# Noctua_2.net
KiCad netlist of a schematic drawn in EAGLE
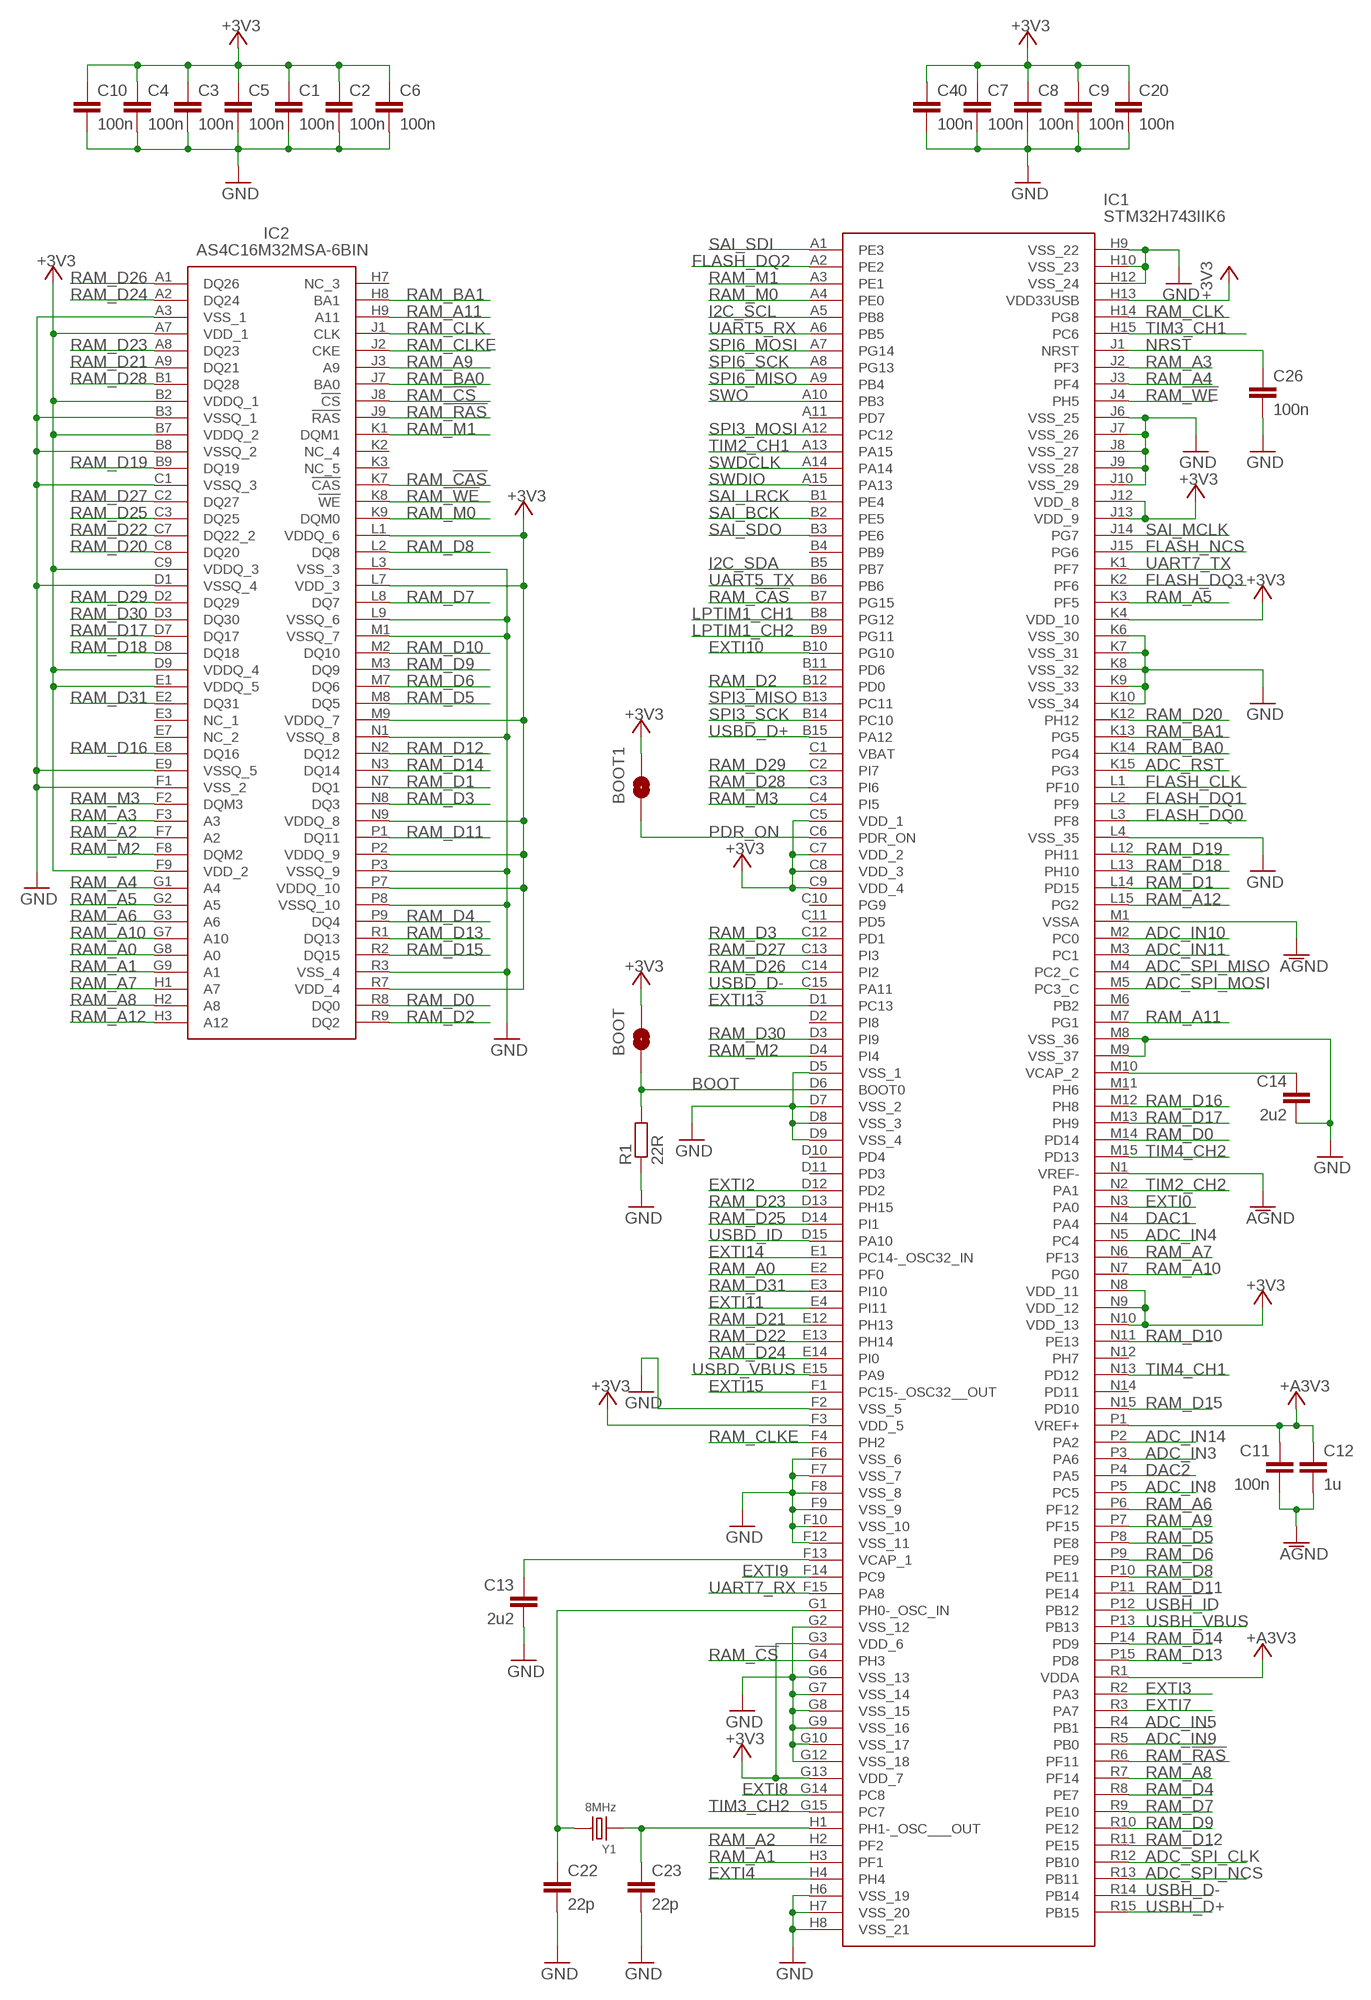
[diagram p0: schematic, sheet 1, part 1 of 2]
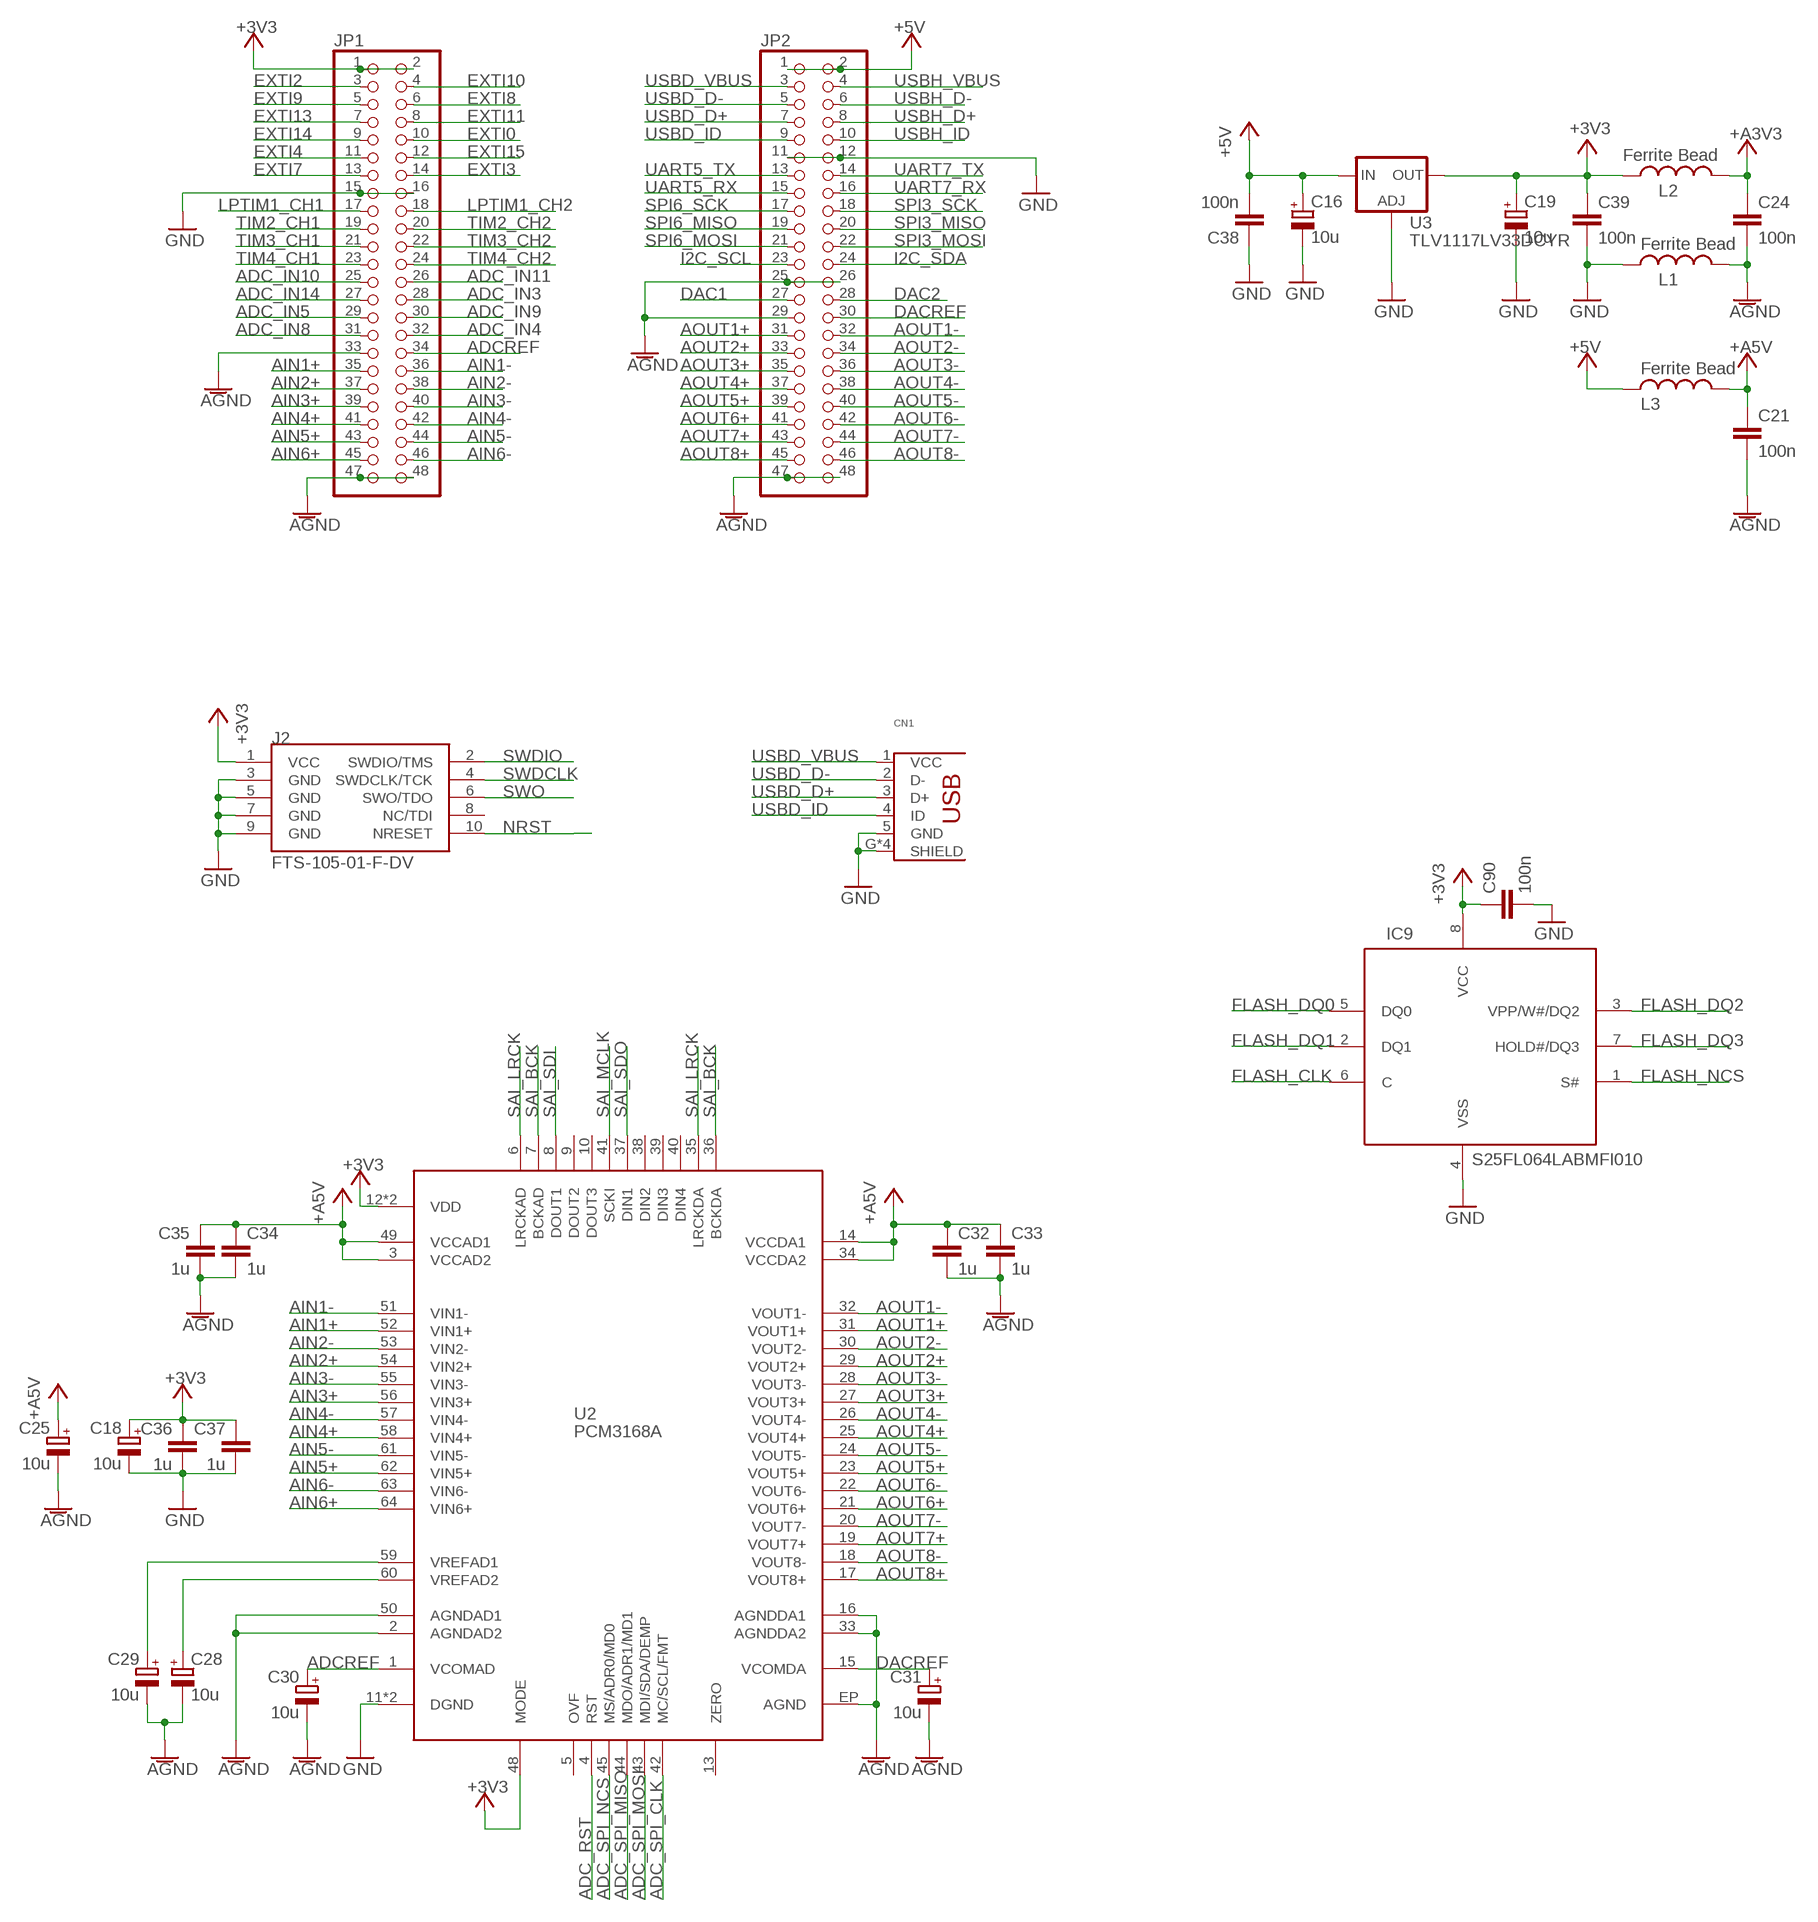
[diagram p1: schematic, sheet 1, part 2 of 2]

(export (version "E")
  (design (tool "Eeschema 10.0.6"))
  (components
    (comp (ref "BOOT")
      (value "SOLDERJUMPERNO")
      (footprint "eagle-import:SJ_2S-NO")
      (libsource (lib "eagle-import") (part "SOLDERJUMPERNO"))
    )
    (comp (ref "BOOT1")
      (value "SOLDERJUMPERNO")
      (footprint "eagle-import:SJ_2S-NO")
      (libsource (lib "eagle-import") (part "SOLDERJUMPERNO"))
    )
    (comp (ref "C1")
      (value "100n")
      (footprint "eagle-import:C0402")
      (libsource (lib "eagle-import") (part "C-EUC0402"))
    )
    (comp (ref "C2")
      (value "100n")
      (footprint "eagle-import:C0402")
      (libsource (lib "eagle-import") (part "C-EUC0402"))
    )
    (comp (ref "C3")
      (value "100n")
      (footprint "eagle-import:C0402")
      (libsource (lib "eagle-import") (part "C-EUC0402"))
    )
    (comp (ref "C4")
      (value "100n")
      (footprint "eagle-import:C0402")
      (libsource (lib "eagle-import") (part "C-EUC0402"))
    )
    (comp (ref "C5")
      (value "100n")
      (footprint "eagle-import:C0402")
      (libsource (lib "eagle-import") (part "C-EUC0402"))
    )
    (comp (ref "C6")
      (value "100n")
      (footprint "eagle-import:C0402")
      (libsource (lib "eagle-import") (part "C-EUC0402"))
    )
    (comp (ref "C7")
      (value "100n")
      (footprint "eagle-import:C0402")
      (libsource (lib "eagle-import") (part "C-EUC0402"))
    )
    (comp (ref "C8")
      (value "100n")
      (footprint "eagle-import:C0402")
      (libsource (lib "eagle-import") (part "C-EUC0402"))
    )
    (comp (ref "C9")
      (value "100n")
      (footprint "eagle-import:C0402")
      (libsource (lib "eagle-import") (part "C-EUC0402"))
    )
    (comp (ref "C10")
      (value "100n")
      (footprint "eagle-import:C0402")
      (libsource (lib "eagle-import") (part "C-EUC0402"))
    )
    (comp (ref "C11")
      (value "100n")
      (footprint "eagle-import:C0402")
      (libsource (lib "eagle-import") (part "C-EUC0402"))
    )
    (comp (ref "C12")
      (value "1u")
      (footprint "eagle-import:C0402")
      (libsource (lib "eagle-import") (part "C-EUC0402"))
    )
    (comp (ref "C13")
      (value "2u2")
      (footprint "eagle-import:C0402")
      (libsource (lib "eagle-import") (part "C-EUC0402"))
    )
    (comp (ref "C14")
      (value "2u2")
      (footprint "eagle-import:C0402")
      (libsource (lib "eagle-import") (part "C-EUC0402"))
    )
    (comp (ref "C16")
      (value "10u")
      (footprint "eagle-import:UD-4X5,8_NICHICON")
      (libsource (lib "eagle-import") (part "CPOL-EUUD-4X5,8"))
    )
    (comp (ref "C18")
      (value "10u")
      (footprint "eagle-import:UD-4X5,8_NICHICON")
      (libsource (lib "eagle-import") (part "CPOL-EUUD-4X5,8"))
    )
    (comp (ref "C19")
      (value "10u")
      (footprint "eagle-import:UD-4X5,8_NICHICON")
      (libsource (lib "eagle-import") (part "CPOL-EUUD-4X5,8"))
    )
    (comp (ref "C20")
      (value "100n")
      (footprint "eagle-import:C0402")
      (libsource (lib "eagle-import") (part "C-EUC0402"))
    )
    (comp (ref "C21")
      (value "100n")
      (footprint "eagle-import:C0603")
      (libsource (lib "eagle-import") (part "C-EUC0603"))
    )
    (comp (ref "C22")
      (value "22p")
      (footprint "eagle-import:C0402")
      (libsource (lib "eagle-import") (part "C-EUC0402"))
    )
    (comp (ref "C23")
      (value "22p")
      (footprint "eagle-import:C0402")
      (libsource (lib "eagle-import") (part "C-EUC0402"))
    )
    (comp (ref "C24")
      (value "100n")
      (footprint "eagle-import:C0402")
      (libsource (lib "eagle-import") (part "C-EUC0402"))
    )
    (comp (ref "C25")
      (value "10u")
      (footprint "eagle-import:UD-4X5,8_NICHICON")
      (libsource (lib "eagle-import") (part "CPOL-EUUD-4X5,8"))
    )
    (comp (ref "C26")
      (value "100n")
      (footprint "eagle-import:C0402")
      (libsource (lib "eagle-import") (part "C-EUC0402"))
    )
    (comp (ref "C28")
      (value "10u")
      (footprint "eagle-import:UD-4X5,8_NICHICON")
      (libsource (lib "eagle-import") (part "CPOL-EUUD-4X5,8"))
    )
    (comp (ref "C29")
      (value "10u")
      (footprint "eagle-import:UD-4X5,8_NICHICON")
      (libsource (lib "eagle-import") (part "CPOL-EUUD-4X5,8"))
    )
    (comp (ref "C30")
      (value "10u")
      (footprint "eagle-import:UD-4X5,8_NICHICON")
      (libsource (lib "eagle-import") (part "CPOL-EUUD-4X5,8"))
    )
    (comp (ref "C31")
      (value "10u")
      (footprint "eagle-import:UD-4X5,8_NICHICON")
      (libsource (lib "eagle-import") (part "CPOL-EUUD-4X5,8"))
    )
    (comp (ref "C32")
      (value "1u")
      (footprint "eagle-import:C0603")
      (libsource (lib "eagle-import") (part "C-EUC0603"))
    )
    (comp (ref "C33")
      (value "1u")
      (footprint "eagle-import:C0603")
      (libsource (lib "eagle-import") (part "C-EUC0603"))
    )
    (comp (ref "C34")
      (value "1u")
      (footprint "eagle-import:C0603")
      (libsource (lib "eagle-import") (part "C-EUC0603"))
    )
    (comp (ref "C35")
      (value "1u")
      (footprint "eagle-import:C0603")
      (libsource (lib "eagle-import") (part "C-EUC0603"))
    )
    (comp (ref "C36")
      (value "1u")
      (footprint "eagle-import:C0603")
      (libsource (lib "eagle-import") (part "C-EUC0603"))
    )
    (comp (ref "C37")
      (value "1u")
      (footprint "eagle-import:C0603")
      (libsource (lib "eagle-import") (part "C-EUC0603"))
    )
    (comp (ref "C38")
      (value "100n")
      (footprint "eagle-import:C0402")
      (libsource (lib "eagle-import") (part "C-EUC0402"))
    )
    (comp (ref "C39")
      (value "100n")
      (footprint "eagle-import:C0402")
      (libsource (lib "eagle-import") (part "C-EUC0402"))
    )
    (comp (ref "C40")
      (value "100n")
      (footprint "eagle-import:C0402")
      (libsource (lib "eagle-import") (part "C-EUC0402"))
    )
    (comp (ref "C90")
      (value "100n")
      (footprint "eagle-import:C0402")
      (libsource (lib "eagle-import") (part "C-EUC0402"))
    )
    (comp (ref "CN1")
      (value "USB_HRS_ZX62-B-5PA(11)MICRO.B")
      (footprint "eagle-import:HRS_ZX62RD-AB-5P8")
      (libsource (lib "eagle-import") (part "USB_HRS_ZX62-B-5PA(11)MICRO.B"))
    )
    (comp (ref "IC1")
      (value "STM32H743IIK6")
      (footprint "eagle-import:BGA201C65P15X15_1000X1000X60")
      (fields (field (name "MOUSER_PART_NUMBER") "511-STM32H743IIK6"))
      (libsource (lib "eagle-import") (part "STM32H743IIK6"))
    )
    (comp (ref "IC2")
      (value "AS4C16M32MSA-6BIN")
      (footprint "eagle-import:BGA90C80P9X15_800X1300X100")
      (fields (field (name "MOUSER_PART_NUMBER") "913-AS4C16M32MSA6BIN"))
      (libsource (lib "eagle-import") (part "AS4C16M32MSA-6BIN"))
    )
    (comp (ref "IC9")
      (value "S25FL064LABMFI010")
      (footprint "eagle-import:SO8W")
      (libsource (lib "eagle-import") (part "N25Q128A13"))
    )
    (comp (ref "J2")
      (value "FTS-105-01-F-DV")
      (footprint "eagle-import:2X5_1.27MM_SMD")
      (libsource (lib "eagle-import") (part "ARM_10SMD"))
    )
    (comp (ref "JP1")
      (value "PINHD-2X24")
      (footprint "eagle-import:2X24")
      (libsource (lib "eagle-import") (part "PINHD-2X24"))
    )
    (comp (ref "JP2")
      (value "PINHD-2X24")
      (footprint "eagle-import:2X24")
      (libsource (lib "eagle-import") (part "PINHD-2X24"))
    )
    (comp (ref "L1")
      (value "Ferrite Bead")
      (footprint "eagle-import:0603")
      (libsource (lib "eagle-import") (part "INDUCTOR"))
    )
    (comp (ref "L2")
      (value "Ferrite Bead")
      (footprint "eagle-import:0603")
      (libsource (lib "eagle-import") (part "INDUCTOR"))
    )
    (comp (ref "L3")
      (value "Ferrite Bead")
      (footprint "eagle-import:0603")
      (libsource (lib "eagle-import") (part "INDUCTOR"))
    )
    (comp (ref "R1")
      (value "22R")
      (footprint "eagle-import:0603")
      (libsource (lib "eagle-import") (part "R-EU_0603"))
    )
    (comp (ref "U2")
      (value "PCM3168A")
      (footprint "eagle-import:PQFP64")
      (libsource (lib "eagle-import") (part "PCM3168A"))
    )
    (comp (ref "U3")
      (value "TLV1117LV33DCYR")
      (footprint "eagle-import:SOT223")
      (libsource (lib "eagle-import") (part "LD117A?S33TR"))
    )
    (comp (ref "Y1")
      (value "8MHz")
      (footprint "eagle-import:X2-SMD-5.0X3.2X1.3MM")
      (fields (field (name "MPN") "5032/2P"))
      (libsource (lib "eagle-import") (part "SMD-CRYSTAL-8MHZ-20PF-20PPM(2P-5.0X3.2MM)"))
    )
  )
  (nets
    (net (code "1") (name "+3V3") (class "Default")
      (node (ref "BOOT") (pin "1") (pinfunction "1_1") (pintype "passive"))
      (node (ref "BOOT1") (pin "1") (pinfunction "1_1") (pintype "passive"))
      (node (ref "C1") (pin "1") (pinfunction "1_1") (pintype "passive"))
      (node (ref "C10") (pin "1") (pinfunction "1_1") (pintype "passive"))
      (node (ref "C18") (pin "+") (pinfunction "+_+") (pintype "passive"))
      (node (ref "C19") (pin "+") (pinfunction "+_+") (pintype "passive"))
      (node (ref "C2") (pin "1") (pinfunction "1_1") (pintype "passive"))
      (node (ref "C20") (pin "1") (pinfunction "1_1") (pintype "passive"))
      (node (ref "C3") (pin "1") (pinfunction "1_1") (pintype "passive"))
      (node (ref "C36") (pin "1") (pinfunction "1_1") (pintype "passive"))
      (node (ref "C37") (pin "1") (pinfunction "1_1") (pintype "passive"))
      (node (ref "C39") (pin "1") (pinfunction "1_1") (pintype "passive"))
      (node (ref "C4") (pin "1") (pinfunction "1_1") (pintype "passive"))
      (node (ref "C40") (pin "1") (pinfunction "1_1") (pintype "passive"))
      (node (ref "C5") (pin "1") (pinfunction "1_1") (pintype "passive"))
      (node (ref "C6") (pin "1") (pinfunction "1_1") (pintype "passive"))
      (node (ref "C7") (pin "1") (pinfunction "1_1") (pintype "passive"))
      (node (ref "C8") (pin "1") (pinfunction "1_1") (pintype "passive"))
      (node (ref "C9") (pin "1") (pinfunction "1_1") (pintype "passive"))
      (node (ref "C90") (pin "1") (pinfunction "1_1") (pintype "passive"))
      (node (ref "IC1") (pin "C5") (pinfunction "VDD_1_C5") (pintype "bidirectional"))
      (node (ref "IC1") (pin "C7") (pinfunction "VDD_2_C7") (pintype "bidirectional"))
      (node (ref "IC1") (pin "C8") (pinfunction "VDD_3_C8") (pintype "bidirectional"))
      (node (ref "IC1") (pin "C9") (pinfunction "VDD_4_C9") (pintype "bidirectional"))
      (node (ref "IC1") (pin "F3") (pinfunction "VDD_5_F3") (pintype "bidirectional"))
      (node (ref "IC1") (pin "G13") (pinfunction "VDD_7_G13") (pintype "bidirectional"))
      (node (ref "IC1") (pin "G3") (pinfunction "VDD_6_G3") (pintype "bidirectional"))
      (node (ref "IC1") (pin "H13") (pinfunction "VDD33USB_H13") (pintype "bidirectional"))
      (node (ref "IC1") (pin "J12") (pinfunction "VDD_8_J12") (pintype "bidirectional"))
      (node (ref "IC1") (pin "J13") (pinfunction "VDD_9_J13") (pintype "bidirectional"))
      (node (ref "IC1") (pin "K4") (pinfunction "VDD_10_K4") (pintype "bidirectional"))
      (node (ref "IC1") (pin "N10") (pinfunction "VDD_13_N10") (pintype "bidirectional"))
      (node (ref "IC1") (pin "N8") (pinfunction "VDD_11_N8") (pintype "bidirectional"))
      (node (ref "IC1") (pin "N9") (pinfunction "VDD_12_N9") (pintype "bidirectional"))
      (node (ref "IC2") (pin "A7") (pinfunction "VDD_1_A7") (pintype "bidirectional"))
      (node (ref "IC2") (pin "B2") (pinfunction "VDDQ_1_B2") (pintype "bidirectional"))
      (node (ref "IC2") (pin "B7") (pinfunction "VDDQ_2_B7") (pintype "bidirectional"))
      (node (ref "IC2") (pin "C9") (pinfunction "VDDQ_3_C9") (pintype "bidirectional"))
      (node (ref "IC2") (pin "D9") (pinfunction "VDDQ_4_D9") (pintype "bidirectional"))
      (node (ref "IC2") (pin "E1") (pinfunction "VDDQ_5_E1") (pintype "bidirectional"))
      (node (ref "IC2") (pin "F9") (pinfunction "VDD_2_F9") (pintype "bidirectional"))
      (node (ref "IC2") (pin "L1") (pinfunction "VDDQ_6_L1") (pintype "bidirectional"))
      (node (ref "IC2") (pin "L7") (pinfunction "VDD_3_L7") (pintype "bidirectional"))
      (node (ref "IC2") (pin "M9") (pinfunction "VDDQ_7_M9") (pintype "bidirectional"))
      (node (ref "IC2") (pin "N9") (pinfunction "VDDQ_8_N9") (pintype "bidirectional"))
      (node (ref "IC2") (pin "P2") (pinfunction "VDDQ_9_P2") (pintype "bidirectional"))
      (node (ref "IC2") (pin "P7") (pinfunction "VDDQ_10_P7") (pintype "bidirectional"))
      (node (ref "IC2") (pin "R7") (pinfunction "VDD_4_R7") (pintype "bidirectional"))
      (node (ref "IC9") (pin "8") (pinfunction "VCC_8") (pintype "bidirectional"))
      (node (ref "J2") (pin "1") (pinfunction "VCC_1") (pintype "bidirectional"))
      (node (ref "JP1") (pin "1") (pinfunction "1_1") (pintype "passive"))
      (node (ref "JP1") (pin "2") (pinfunction "2_2") (pintype "passive"))
      (node (ref "L2") (pin "2") (pinfunction "2_2") (pintype "passive"))
      (node (ref "U2") (pin "12") (pinfunction "VDD_12") (pintype "bidirectional"))
      (node (ref "U2") (pin "46") (pinfunction "VDD_46") (pintype "bidirectional"))
      (node (ref "U2") (pin "48") (pinfunction "MODE_48") (pintype "bidirectional"))
      (node (ref "U3") (pin "4") (pinfunction "OUT_4") (pintype "passive"))
    )
    (net (code "2") (name "+5V") (class "Default")
      (node (ref "C16") (pin "+") (pinfunction "+_+") (pintype "passive"))
      (node (ref "C38") (pin "2") (pinfunction "2_2") (pintype "passive"))
      (node (ref "JP2") (pin "1") (pinfunction "1_1") (pintype "passive"))
      (node (ref "JP2") (pin "2") (pinfunction "2_2") (pintype "passive"))
      (node (ref "L3") (pin "2") (pinfunction "2_2") (pintype "passive"))
      (node (ref "U3") (pin "3") (pinfunction "IN_3") (pintype "input"))
    )
    (net (code "3") (name "+A3V3") (class "Default")
      (node (ref "C11") (pin "1") (pinfunction "1_1") (pintype "passive"))
      (node (ref "C12") (pin "1") (pinfunction "1_1") (pintype "passive"))
      (node (ref "C24") (pin "1") (pinfunction "1_1") (pintype "passive"))
      (node (ref "IC1") (pin "P1") (pinfunction "VREF+_P1") (pintype "bidirectional"))
      (node (ref "IC1") (pin "R1") (pinfunction "VDDA_R1") (pintype "bidirectional"))
      (node (ref "L2") (pin "1") (pinfunction "1_1") (pintype "passive"))
    )
    (net (code "4") (name "+A5V") (class "Default")
      (node (ref "C21") (pin "1") (pinfunction "1_1") (pintype "passive"))
      (node (ref "C25") (pin "+") (pinfunction "+_+") (pintype "passive"))
      (node (ref "C32") (pin "1") (pinfunction "1_1") (pintype "passive"))
      (node (ref "C33") (pin "1") (pinfunction "1_1") (pintype "passive"))
      (node (ref "C34") (pin "1") (pinfunction "1_1") (pintype "passive"))
      (node (ref "C35") (pin "1") (pinfunction "1_1") (pintype "passive"))
      (node (ref "L3") (pin "1") (pinfunction "1_1") (pintype "passive"))
      (node (ref "U2") (pin "14") (pinfunction "VCCDA1_14") (pintype "bidirectional"))
      (node (ref "U2") (pin "3") (pinfunction "VCCAD2_3") (pintype "bidirectional"))
      (node (ref "U2") (pin "34") (pinfunction "VCCDA2_34") (pintype "bidirectional"))
      (node (ref "U2") (pin "49") (pinfunction "VCCAD1_49") (pintype "bidirectional"))
    )
    (net (code "5") (name "/ADCREF") (class "Default")
      (node (ref "C30") (pin "+") (pinfunction "+_+") (pintype "passive"))
      (node (ref "JP1") (pin "34") (pinfunction "34_34") (pintype "passive"))
      (node (ref "U2") (pin "1") (pinfunction "VCOMAD_1") (pintype "bidirectional"))
    )
    (net (code "6") (name "/ADC_IN3") (class "Default")
      (node (ref "IC1") (pin "P3") (pinfunction "PA6_P3") (pintype "bidirectional"))
      (node (ref "JP1") (pin "28") (pinfunction "28_28") (pintype "passive"))
    )
    (net (code "7") (name "/ADC_IN4") (class "Default")
      (node (ref "IC1") (pin "N5") (pinfunction "PC4_N5") (pintype "bidirectional"))
      (node (ref "JP1") (pin "32") (pinfunction "32_32") (pintype "passive"))
    )
    (net (code "8") (name "/ADC_IN5") (class "Default")
      (node (ref "IC1") (pin "R4") (pinfunction "PB1_R4") (pintype "bidirectional"))
      (node (ref "JP1") (pin "29") (pinfunction "29_29") (pintype "passive"))
    )
    (net (code "9") (name "/ADC_IN8") (class "Default")
      (node (ref "IC1") (pin "P5") (pinfunction "PC5_P5") (pintype "bidirectional"))
      (node (ref "JP1") (pin "31") (pinfunction "31_31") (pintype "passive"))
    )
    (net (code "10") (name "/ADC_IN9") (class "Default")
      (node (ref "IC1") (pin "R5") (pinfunction "PB0_R5") (pintype "bidirectional"))
      (node (ref "JP1") (pin "30") (pinfunction "30_30") (pintype "passive"))
    )
    (net (code "11") (name "/ADC_IN10") (class "Default")
      (node (ref "IC1") (pin "M2") (pinfunction "PC0_M2") (pintype "bidirectional"))
      (node (ref "JP1") (pin "25") (pinfunction "25_25") (pintype "passive"))
    )
    (net (code "12") (name "/ADC_IN11") (class "Default")
      (node (ref "IC1") (pin "M3") (pinfunction "PC1_M3") (pintype "bidirectional"))
      (node (ref "JP1") (pin "26") (pinfunction "26_26") (pintype "passive"))
    )
    (net (code "13") (name "/ADC_IN14") (class "Default")
      (node (ref "IC1") (pin "P2") (pinfunction "PA2_P2") (pintype "bidirectional"))
      (node (ref "JP1") (pin "27") (pinfunction "27_27") (pintype "passive"))
    )
    (net (code "14") (name "/ADC_RST") (class "Default")
      (node (ref "IC1") (pin "K15") (pinfunction "PG3_K15") (pintype "bidirectional"))
      (node (ref "U2") (pin "4") (pinfunction "RST_4") (pintype "bidirectional"))
    )
    (net (code "15") (name "/ADC_SPI_CLK") (class "Default")
      (node (ref "IC1") (pin "R12") (pinfunction "PB10_R12") (pintype "bidirectional"))
      (node (ref "U2") (pin "42") (pinfunction "MC/SCL/FMT_42") (pintype "bidirectional"))
    )
    (net (code "16") (name "/ADC_SPI_MISO") (class "Default")
      (node (ref "IC1") (pin "M4") (pinfunction "PC2_C_M4") (pintype "bidirectional"))
      (node (ref "U2") (pin "44") (pinfunction "MDO/ADR1/MD1_44") (pintype "bidirectional"))
    )
    (net (code "17") (name "/ADC_SPI_MOSI") (class "Default")
      (node (ref "IC1") (pin "M5") (pinfunction "PC3_C_M5") (pintype "bidirectional"))
      (node (ref "U2") (pin "43") (pinfunction "MDI/SDA/DEMP_43") (pintype "bidirectional"))
    )
    (net (code "18") (name "/ADC_SPI_NCS") (class "Default")
      (node (ref "IC1") (pin "R13") (pinfunction "PB11_R13") (pintype "bidirectional"))
      (node (ref "U2") (pin "45") (pinfunction "MS/ADR0/MD0_45") (pintype "bidirectional"))
    )
    (net (code "19") (name "/AIN1+") (class "Default")
      (node (ref "JP1") (pin "35") (pinfunction "35_35") (pintype "passive"))
      (node (ref "U2") (pin "52") (pinfunction "VIN1+_52") (pintype "bidirectional"))
    )
    (net (code "20") (name "/AIN1-") (class "Default")
      (node (ref "JP1") (pin "36") (pinfunction "36_36") (pintype "passive"))
      (node (ref "U2") (pin "51") (pinfunction "VIN1-_51") (pintype "bidirectional"))
    )
    (net (code "21") (name "/AIN2+") (class "Default")
      (node (ref "JP1") (pin "37") (pinfunction "37_37") (pintype "passive"))
      (node (ref "U2") (pin "54") (pinfunction "VIN2+_54") (pintype "bidirectional"))
    )
    (net (code "22") (name "/AIN2-") (class "Default")
      (node (ref "JP1") (pin "38") (pinfunction "38_38") (pintype "passive"))
      (node (ref "U2") (pin "53") (pinfunction "VIN2-_53") (pintype "bidirectional"))
    )
    (net (code "23") (name "/AIN3+") (class "Default")
      (node (ref "JP1") (pin "39") (pinfunction "39_39") (pintype "passive"))
      (node (ref "U2") (pin "56") (pinfunction "VIN3+_56") (pintype "bidirectional"))
    )
    (net (code "24") (name "/AIN3-") (class "Default")
      (node (ref "JP1") (pin "40") (pinfunction "40_40") (pintype "passive"))
      (node (ref "U2") (pin "55") (pinfunction "VIN3-_55") (pintype "bidirectional"))
    )
    (net (code "25") (name "/AIN4+") (class "Default")
      (node (ref "JP1") (pin "41") (pinfunction "41_41") (pintype "passive"))
      (node (ref "U2") (pin "58") (pinfunction "VIN4+_58") (pintype "bidirectional"))
    )
    (net (code "26") (name "/AIN4-") (class "Default")
      (node (ref "JP1") (pin "42") (pinfunction "42_42") (pintype "passive"))
      (node (ref "U2") (pin "57") (pinfunction "VIN4-_57") (pintype "bidirectional"))
    )
    (net (code "27") (name "/AIN5+") (class "Default")
      (node (ref "JP1") (pin "43") (pinfunction "43_43") (pintype "passive"))
      (node (ref "U2") (pin "62") (pinfunction "VIN5+_62") (pintype "bidirectional"))
    )
    (net (code "28") (name "/AIN5-") (class "Default")
      (node (ref "JP1") (pin "44") (pinfunction "44_44") (pintype "passive"))
      (node (ref "U2") (pin "61") (pinfunction "VIN5-_61") (pintype "bidirectional"))
    )
    (net (code "29") (name "/AIN6+") (class "Default")
      (node (ref "JP1") (pin "45") (pinfunction "45_45") (pintype "passive"))
      (node (ref "U2") (pin "64") (pinfunction "VIN6+_64") (pintype "bidirectional"))
    )
    (net (code "30") (name "/AIN6-") (class "Default")
      (node (ref "JP1") (pin "46") (pinfunction "46_46") (pintype "passive"))
      (node (ref "U2") (pin "63") (pinfunction "VIN6-_63") (pintype "bidirectional"))
    )
    (net (code "31") (name "/AOUT1+") (class "Default")
      (node (ref "JP2") (pin "31") (pinfunction "31_31") (pintype "passive"))
      (node (ref "U2") (pin "31") (pinfunction "VOUT1+_31") (pintype "bidirectional"))
    )
    (net (code "32") (name "/AOUT1-") (class "Default")
      (node (ref "JP2") (pin "32") (pinfunction "32_32") (pintype "passive"))
      (node (ref "U2") (pin "32") (pinfunction "VOUT1-_32") (pintype "bidirectional"))
    )
    (net (code "33") (name "/AOUT2+") (class "Default")
      (node (ref "JP2") (pin "33") (pinfunction "33_33") (pintype "passive"))
      (node (ref "U2") (pin "29") (pinfunction "VOUT2+_29") (pintype "bidirectional"))
    )
    (net (code "34") (name "/AOUT2-") (class "Default")
      (node (ref "JP2") (pin "34") (pinfunction "34_34") (pintype "passive"))
      (node (ref "U2") (pin "30") (pinfunction "VOUT2-_30") (pintype "bidirectional"))
    )
    (net (code "35") (name "/AOUT3+") (class "Default")
      (node (ref "JP2") (pin "35") (pinfunction "35_35") (pintype "passive"))
      (node (ref "U2") (pin "27") (pinfunction "VOUT3+_27") (pintype "bidirectional"))
    )
    (net (code "36") (name "/AOUT3-") (class "Default")
      (node (ref "JP2") (pin "36") (pinfunction "36_36") (pintype "passive"))
      (node (ref "U2") (pin "28") (pinfunction "VOUT3-_28") (pintype "bidirectional"))
    )
    (net (code "37") (name "/AOUT4+") (class "Default")
      (node (ref "JP2") (pin "37") (pinfunction "37_37") (pintype "passive"))
      (node (ref "U2") (pin "25") (pinfunction "VOUT4+_25") (pintype "bidirectional"))
    )
    (net (code "38") (name "/AOUT4-") (class "Default")
      (node (ref "JP2") (pin "38") (pinfunction "38_38") (pintype "passive"))
      (node (ref "U2") (pin "26") (pinfunction "VOUT4-_26") (pintype "bidirectional"))
    )
    (net (code "39") (name "/AOUT5+") (class "Default")
      (node (ref "JP2") (pin "39") (pinfunction "39_39") (pintype "passive"))
      (node (ref "U2") (pin "23") (pinfunction "VOUT5+_23") (pintype "bidirectional"))
    )
    (net (code "40") (name "/AOUT5-") (class "Default")
      (node (ref "JP2") (pin "40") (pinfunction "40_40") (pintype "passive"))
      (node (ref "U2") (pin "24") (pinfunction "VOUT5-_24") (pintype "bidirectional"))
    )
    (net (code "41") (name "/AOUT6+") (class "Default")
      (node (ref "JP2") (pin "41") (pinfunction "41_41") (pintype "passive"))
      (node (ref "U2") (pin "21") (pinfunction "VOUT6+_21") (pintype "bidirectional"))
    )
    (net (code "42") (name "/AOUT6-") (class "Default")
      (node (ref "JP2") (pin "42") (pinfunction "42_42") (pintype "passive"))
      (node (ref "U2") (pin "22") (pinfunction "VOUT6-_22") (pintype "bidirectional"))
    )
    (net (code "43") (name "/AOUT7+") (class "Default")
      (node (ref "JP2") (pin "43") (pinfunction "43_43") (pintype "passive"))
      (node (ref "U2") (pin "19") (pinfunction "VOUT7+_19") (pintype "bidirectional"))
    )
    (net (code "44") (name "/AOUT7-") (class "Default")
      (node (ref "JP2") (pin "44") (pinfunction "44_44") (pintype "passive"))
      (node (ref "U2") (pin "20") (pinfunction "VOUT7-_20") (pintype "bidirectional"))
    )
    (net (code "45") (name "/AOUT8+") (class "Default")
      (node (ref "JP2") (pin "45") (pinfunction "45_45") (pintype "passive"))
      (node (ref "U2") (pin "17") (pinfunction "VOUT8+_17") (pintype "bidirectional"))
    )
    (net (code "46") (name "/AOUT8-") (class "Default")
      (node (ref "JP2") (pin "46") (pinfunction "46_46") (pintype "passive"))
      (node (ref "U2") (pin "18") (pinfunction "VOUT8-_18") (pintype "bidirectional"))
    )
    (net (code "47") (name "/BOOT") (class "Default")
      (node (ref "BOOT") (pin "2") (pinfunction "2_2") (pintype "passive"))
      (node (ref "IC1") (pin "D6") (pinfunction "BOOT0_D6") (pintype "bidirectional"))
      (node (ref "R1") (pin "2") (pinfunction "2_2") (pintype "passive"))
    )
    (net (code "48") (name "/DAC1") (class "Default")
      (node (ref "IC1") (pin "N4") (pinfunction "PA4_N4") (pintype "bidirectional"))
      (node (ref "JP2") (pin "27") (pinfunction "27_27") (pintype "passive"))
    )
    (net (code "49") (name "/DAC2") (class "Default")
      (node (ref "IC1") (pin "P4") (pinfunction "PA5_P4") (pintype "bidirectional"))
      (node (ref "JP2") (pin "28") (pinfunction "28_28") (pintype "passive"))
    )
    (net (code "50") (name "/DACREF") (class "Default")
      (node (ref "C31") (pin "+") (pinfunction "+_+") (pintype "passive"))
      (node (ref "JP2") (pin "30") (pinfunction "30_30") (pintype "passive"))
      (node (ref "U2") (pin "15") (pinfunction "VCOMDA_15") (pintype "bidirectional"))
    )
    (net (code "51") (name "/EXTI0") (class "Default")
      (node (ref "IC1") (pin "N3") (pinfunction "PA0_N3") (pintype "bidirectional"))
      (node (ref "JP1") (pin "10") (pinfunction "10_10") (pintype "passive"))
    )
    (net (code "52") (name "/EXTI2") (class "Default")
      (node (ref "IC1") (pin "D12") (pinfunction "PD2_D12") (pintype "bidirectional"))
      (node (ref "JP1") (pin "3") (pinfunction "3_3") (pintype "passive"))
    )
    (net (code "53") (name "/EXTI3") (class "Default")
      (node (ref "IC1") (pin "R2") (pinfunction "PA3_R2") (pintype "bidirectional"))
      (node (ref "JP1") (pin "14") (pinfunction "14_14") (pintype "passive"))
    )
    (net (code "54") (name "/EXTI4") (class "Default")
      (node (ref "IC1") (pin "H4") (pinfunction "PH4_H4") (pintype "bidirectional"))
      (node (ref "JP1") (pin "11") (pinfunction "11_11") (pintype "passive"))
    )
    (net (code "55") (name "/EXTI7") (class "Default")
      (node (ref "IC1") (pin "R3") (pinfunction "PA7_R3") (pintype "bidirectional"))
      (node (ref "JP1") (pin "13") (pinfunction "13_13") (pintype "passive"))
    )
    (net (code "56") (name "/EXTI8") (class "Default")
      (node (ref "IC1") (pin "G14") (pinfunction "PC8_G14") (pintype "bidirectional"))
      (node (ref "JP1") (pin "6") (pinfunction "6_6") (pintype "passive"))
    )
    (net (code "57") (name "/EXTI9") (class "Default")
      (node (ref "IC1") (pin "F14") (pinfunction "PC9_F14") (pintype "bidirectional"))
      (node (ref "JP1") (pin "5") (pinfunction "5_5") (pintype "passive"))
    )
    (net (code "58") (name "/EXTI10") (class "Default")
      (node (ref "IC1") (pin "B10") (pinfunction "PG10_B10") (pintype "bidirectional"))
      (node (ref "JP1") (pin "4") (pinfunction "4_4") (pintype "passive"))
    )
    (net (code "59") (name "/EXTI11") (class "Default")
      (node (ref "IC1") (pin "E4") (pinfunction "PI11_E4") (pintype "bidirectional"))
      (node (ref "JP1") (pin "8") (pinfunction "8_8") (pintype "passive"))
    )
    (net (code "60") (name "/EXTI13") (class "Default")
      (node (ref "IC1") (pin "D1") (pinfunction "PC13_D1") (pintype "bidirectional"))
      (node (ref "JP1") (pin "7") (pinfunction "7_7") (pintype "passive"))
    )
    (net (code "61") (name "/EXTI14") (class "Default")
      (node (ref "IC1") (pin "E1") (pinfunction "PC14-_OSC32_IN_E1") (pintype "bidirectional"))
      (node (ref "JP1") (pin "9") (pinfunction "9_9") (pintype "passive"))
    )
    (net (code "62") (name "/EXTI15") (class "Default")
      (node (ref "IC1") (pin "F1") (pinfunction "PC15-_OSC32__OUT_F1") (pintype "bidirectional"))
      (node (ref "JP1") (pin "12") (pinfunction "12_12") (pintype "passive"))
    )
    (net (code "63") (name "/FLASH_CLK") (class "Default")
      (node (ref "IC1") (pin "L1") (pinfunction "PF10_L1") (pintype "bidirectional"))
      (node (ref "IC9") (pin "6") (pinfunction "C_6") (pintype "bidirectional"))
    )
    (net (code "64") (name "/FLASH_DQ0") (class "Default")
      (node (ref "IC1") (pin "L3") (pinfunction "PF8_L3") (pintype "bidirectional"))
      (node (ref "IC9") (pin "5") (pinfunction "DQ0_5") (pintype "bidirectional"))
    )
    (net (code "65") (name "/FLASH_DQ1") (class "Default")
      (node (ref "IC1") (pin "L2") (pinfunction "PF9_L2") (pintype "bidirectional"))
      (node (ref "IC9") (pin "2") (pinfunction "DQ1_2") (pintype "bidirectional"))
    )
    (net (code "66") (name "/FLASH_DQ2") (class "Default")
      (node (ref "IC1") (pin "A2") (pinfunction "PE2_A2") (pintype "bidirectional"))
      (node (ref "IC9") (pin "3") (pinfunction "VPP/W#/DQ2_3") (pintype "bidirectional"))
    )
    (net (code "67") (name "/FLASH_DQ3") (class "Default")
      (node (ref "IC1") (pin "K2") (pinfunction "PF6_K2") (pintype "bidirectional"))
      (node (ref "IC9") (pin "7") (pinfunction "HOLD#/DQ3_7") (pintype "bidirectional"))
    )
    (net (code "68") (name "/FLASH_NCS") (class "Default")
      (node (ref "IC1") (pin "J15") (pinfunction "PG6_J15") (pintype "bidirectional"))
      (node (ref "IC9") (pin "1") (pinfunction "S#_1") (pintype "bidirectional"))
    )
    (net (code "69") (name "/I2C_SCL") (class "Default")
      (node (ref "IC1") (pin "A5") (pinfunction "PB8_A5") (pintype "bidirectional"))
      (node (ref "JP2") (pin "23") (pinfunction "23_23") (pintype "passive"))
    )
    (net (code "70") (name "/I2C_SDA") (class "Default")
      (node (ref "IC1") (pin "B5") (pinfunction "PB7_B5") (pintype "bidirectional"))
      (node (ref "JP2") (pin "24") (pinfunction "24_24") (pintype "passive"))
    )
    (net (code "71") (name "/LPTIM1_CH1") (class "Default")
      (node (ref "IC1") (pin "B8") (pinfunction "PG12_B8") (pintype "bidirectional"))
      (node (ref "JP1") (pin "17") (pinfunction "17_17") (pintype "passive"))
    )
    (net (code "72") (name "/LPTIM1_CH2") (class "Default")
      (node (ref "IC1") (pin "B9") (pinfunction "PG11_B9") (pintype "bidirectional"))
      (node (ref "JP1") (pin "18") (pinfunction "18_18") (pintype "passive"))
    )
    (net (code "73") (name "/NRST") (class "Default")
      (node (ref "C26") (pin "1") (pinfunction "1_1") (pintype "passive"))
      (node (ref "IC1") (pin "J1") (pinfunction "NRST_J1") (pintype "bidirectional"))
      (node (ref "J2") (pin "10") (pinfunction "NRESET_10") (pintype "bidirectional"))
    )
    (net (code "74") (name "/PDR_ON") (class "Default")
      (node (ref "BOOT1") (pin "2") (pinfunction "2_2") (pintype "passive"))
      (node (ref "IC1") (pin "C6") (pinfunction "PDR_ON_C6") (pintype "bidirectional"))
    )
    (net (code "75") (name "/RAM_A0") (class "Default")
      (node (ref "IC1") (pin "E2") (pinfunction "PF0_E2") (pintype "bidirectional"))
      (node (ref "IC2") (pin "G8") (pinfunction "A0_G8") (pintype "bidirectional"))
    )
    (net (code "76") (name "/RAM_A1") (class "Default")
      (node (ref "IC1") (pin "H3") (pinfunction "PF1_H3") (pintype "bidirectional"))
      (node (ref "IC2") (pin "G9") (pinfunction "A1_G9") (pintype "bidirectional"))
    )
    (net (code "77") (name "/RAM_A2") (class "Default")
      (node (ref "IC1") (pin "H2") (pinfunction "PF2_H2") (pintype "bidirectional"))
      (node (ref "IC2") (pin "F7") (pinfunction "A2_F7") (pintype "bidirectional"))
    )
    (net (code "78") (name "/RAM_A3") (class "Default")
      (node (ref "IC1") (pin "J2") (pinfunction "PF3_J2") (pintype "bidirectional"))
      (node (ref "IC2") (pin "F3") (pinfunction "A3_F3") (pintype "bidirectional"))
    )
    (net (code "79") (name "/RAM_A4") (class "Default")
      (node (ref "IC1") (pin "J3") (pinfunction "PF4_J3") (pintype "bidirectional"))
      (node (ref "IC2") (pin "G1") (pinfunction "A4_G1") (pintype "bidirectional"))
    )
    (net (code "80") (name "/RAM_A5") (class "Default")
      (node (ref "IC1") (pin "K3") (pinfunction "PF5_K3") (pintype "bidirectional"))
      (node (ref "IC2") (pin "G2") (pinfunction "A5_G2") (pintype "bidirectional"))
    )
    (net (code "81") (name "/RAM_A6") (class "Default")
      (node (ref "IC1") (pin "P6") (pinfunction "PF12_P6") (pintype "bidirectional"))
      (node (ref "IC2") (pin "G3") (pinfunction "A6_G3") (pintype "bidirectional"))
    )
    (net (code "82") (name "/RAM_A7") (class "Default")
      (node (ref "IC1") (pin "N6") (pinfunction "PF13_N6") (pintype "bidirectional"))
      (node (ref "IC2") (pin "H1") (pinfunction "A7_H1") (pintype "bidirectional"))
    )
    (net (code "83") (name "/RAM_A8") (class "Default")
      (node (ref "IC1") (pin "R7") (pinfunction "PF14_R7") (pintype "bidirectional"))
      (node (ref "IC2") (pin "H2") (pinfunction "A8_H2") (pintype "bidirectional"))
    )
    (net (code "84") (name "/RAM_A9") (class "Default")
      (node (ref "IC1") (pin "P7") (pinfunction "PF15_P7") (pintype "bidirectional"))
      (node (ref "IC2") (pin "J3") (pinfunction "A9_J3") (pintype "bidirectional"))
    )
    (net (code "85") (name "/RAM_A10") (class "Default")
      (node (ref "IC1") (pin "N7") (pinfunction "PG0_N7") (pintype "bidirectional"))
      (node (ref "IC2") (pin "G7") (pinfunction "A10_G7") (pintype "bidirectional"))
    )
    (net (code "86") (name "/RAM_A11") (class "Default")
      (node (ref "IC1") (pin "M7") (pinfunction "PG1_M7") (pintype "bidirectional"))
      (node (ref "IC2") (pin "H9") (pinfunction "A11_H9") (pintype "bidirectional"))
    )
    (net (code "87") (name "/RAM_A12") (class "Default")
      (node (ref "IC1") (pin "L15") (pinfunction "PG2_L15") (pintype "bidirectional"))
      (node (ref "IC2") (pin "H3") (pinfunction "A12_H3") (pintype "bidirectional"))
    )
    (net (code "88") (name "/RAM_BA0") (class "Default")
      (node (ref "IC1") (pin "K14") (pinfunction "PG4_K14") (pintype "bidirectional"))
      (node (ref "IC2") (pin "J7") (pinfunction "BA0_J7") (pintype "bidirectional"))
    )
    (net (code "89") (name "/RAM_BA1") (class "Default")
      (node (ref "IC1") (pin "K13") (pinfunction "PG5_K13") (pintype "bidirectional"))
      (node (ref "IC2") (pin "H8") (pinfunction "BA1_H8") (pintype "bidirectional"))
    )
    (net (code "90") (name "/RAM_CLK") (class "Default")
      (node (ref "IC1") (pin "H14") (pinfunction "PG8_H14") (pintype "bidirectional"))
      (node (ref "IC2") (pin "J1") (pinfunction "CLK_J1") (pintype "bidirectional"))
    )
    (net (code "91") (name "/RAM_CLKE") (class "Default")
      (node (ref "IC1") (pin "F4") (pinfunction "PH2_F4") (pintype "bidirectional"))
      (node (ref "IC2") (pin "J2") (pinfunction "CKE_J2") (pintype "bidirectional"))
    )
    (net (code "92") (name "/RAM_D0") (class "Default")
      (node (ref "IC1") (pin "M14") (pinfunction "PD14_M14") (pintype "bidirectional"))
      (node (ref "IC2") (pin "R8") (pinfunction "DQ0_R8") (pintype "bidirectional"))
    )
    (net (code "93") (name "/RAM_D1") (class "Default")
      (node (ref "IC1") (pin "L14") (pinfunction "PD15_L14") (pintype "bidirectional"))
      (node (ref "IC2") (pin "N7") (pinfunction "DQ1_N7") (pintype "bidirectional"))
    )
    (net (code "94") (name "/RAM_D2") (class "Default")
      (node (ref "IC1") (pin "B12") (pinfunction "PD0_B12") (pintype "bidirectional"))
      (node (ref "IC2") (pin "R9") (pinfunction "DQ2_R9") (pintype "bidirectional"))
    )
    (net (code "95") (name "/RAM_D3") (class "Default")
      (node (ref "IC1") (pin "C12") (pinfunction "PD1_C12") (pintype "bidirectional"))
      (node (ref "IC2") (pin "N8") (pinfunction "DQ3_N8") (pintype "bidirectional"))
    )
    (net (code "96") (name "/RAM_D4") (class "Default")
      (node (ref "IC1") (pin "R8") (pinfunction "PE7_R8") (pintype "bidirectional"))
      (node (ref "IC2") (pin "P9") (pinfunction "DQ4_P9") (pintype "bidirectional"))
    )
    (net (code "97") (name "/RAM_D5") (class "Default")
      (node (ref "IC1") (pin "P8") (pinfunction "PE8_P8") (pintype "bidirectional"))
      (node (ref "IC2") (pin "M8") (pinfunction "DQ5_M8") (pintype "bidirectional"))
    )
    (net (code "98") (name "/RAM_D6") (class "Default")
      (node (ref "IC1") (pin "P9") (pinfunction "PE9_P9") (pintype "bidirectional"))
      (node (ref "IC2") (pin "M7") (pinfunction "DQ6_M7") (pintype "bidirectional"))
    )
    (net (code "99") (name "/RAM_D7") (class "Default")
      (node (ref "IC1") (pin "R9") (pinfunction "PE10_R9") (pintype "bidirectional"))
      (node (ref "IC2") (pin "L8") (pinfunction "DQ7_L8") (pintype "bidirectional"))
    )
    (net (code "100") (name "/RAM_D8") (class "Default")
      (node (ref "IC1") (pin "P10") (pinfunction "PE11_P10") (pintype "bidirectional"))
      (node (ref "IC2") (pin "L2") (pinfunction "DQ8_L2") (pintype "bidirectional"))
    )
    (net (code "101") (name "/RAM_D9") (class "Default")
      (node (ref "IC1") (pin "R10") (pinfunction "PE12_R10") (pintype "bidirectional"))
      (node (ref "IC2") (pin "M3") (pinfunction "DQ9_M3") (pintype "bidirectional"))
    )
    (net (code "102") (name "/RAM_D10") (class "Default")
      (node (ref "IC1") (pin "N11") (pinfunction "PE13_N11") (pintype "bidirectional"))
      (node (ref "IC2") (pin "M2") (pinfunction "DQ10_M2") (pintype "bidirectional"))
    )
    (net (code "103") (name "/RAM_D11") (class "Default")
      (node (ref "IC1") (pin "P11") (pinfunction "PE14_P11") (pintype "bidirectional"))
      (node (ref "IC2") (pin "P1") (pinfunction "DQ11_P1") (pintype "bidirectional"))
    )
    (net (code "104") (name "/RAM_D12") (class "Default")
      (node (ref "IC1") (pin "R11") (pinfunction "PE15_R11") (pintype "bidirectional"))
      (node (ref "IC2") (pin "N2") (pinfunction "DQ12_N2") (pintype "bidirectional"))
    )
    (net (code "105") (name "/RAM_D13") (class "Default")
      (node (ref "IC1") (pin "P15") (pinfunction "PD8_P15") (pintype "bidirectional"))
      (node (ref "IC2") (pin "R1") (pinfunction "DQ13_R1") (pintype "bidirectional"))
    )
    (net (code "106") (name "/RAM_D14") (class "Default")
      (node (ref "IC1") (pin "P14") (pinfunction "PD9_P14") (pintype "bidirectional"))
      (node (ref "IC2") (pin "N3") (pinfunction "DQ14_N3") (pintype "bidirectional"))
    )
    (net (code "107") (name "/RAM_D15") (class "Default")
      (node (ref "IC1") (pin "N15") (pinfunction "PD10_N15") (pintype "bidirectional"))
      (node (ref "IC2") (pin "R2") (pinfunction "DQ15_R2") (pintype "bidirectional"))
    )
    (net (code "108") (name "/RAM_D16") (class "Default")
      (node (ref "IC1") (pin "M12") (pinfunction "PH8_M12") (pintype "bidirectional"))
      (node (ref "IC2") (pin "E8") (pinfunction "DQ16_E8") (pintype "bidirectional"))
    )
    (net (code "109") (name "/RAM_D17") (class "Default")
      (node (ref "IC1") (pin "M13") (pinfunction "PH9_M13") (pintype "bidirectional"))
      (node (ref "IC2") (pin "D7") (pinfunction "DQ17_D7") (pintype "bidirectional"))
    )
    (net (code "110") (name "/RAM_D18") (class "Default")
      (node (ref "IC1") (pin "L13") (pinfunction "PH10_L13") (pintype "bidirectional"))
      (node (ref "IC2") (pin "D8") (pinfunction "DQ18_D8") (pintype "bidirectional"))
    )
    (net (code "111") (name "/RAM_D19") (class "Default")
      (node (ref "IC1") (pin "L12") (pinfunction "PH11_L12") (pintype "bidirectional"))
      (node (ref "IC2") (pin "B9") (pinfunction "DQ19_B9") (pintype "bidirectional"))
    )
    (net (code "112") (name "/RAM_D20") (class "Default")
      (node (ref "IC1") (pin "K12") (pinfunction "PH12_K12") (pintype "bidirectional"))
      (node (ref "IC2") (pin "C8") (pinfunction "DQ20_C8") (pintype "bidirectional"))
    )
    (net (code "113") (name "/RAM_D21") (class "Default")
      (node (ref "IC1") (pin "E12") (pinfunction "PH13_E12") (pintype "bidirectional"))
      (node (ref "IC2") (pin "A9") (pinfunction "DQ21_A9") (pintype "bidirectional"))
    )
    (net (code "114") (name "/RAM_D22") (class "Default")
      (node (ref "IC1") (pin "E13") (pinfunction "PH14_E13") (pintype "bidirectional"))
      (node (ref "IC2") (pin "C7") (pinfunction "DQ22_2_C7") (pintype "bidirectional"))
    )
    (net (code "115") (name "/RAM_D23") (class "Default")
      (node (ref "IC1") (pin "D13") (pinfunction "PH15_D13") (pintype "bidirectional"))
      (node (ref "IC2") (pin "A8") (pinfunction "DQ23_A8") (pintype "bidirectional"))
    )
    (net (code "116") (name "/RAM_D24") (class "Default")
      (node (ref "IC1") (pin "E14") (pinfunction "PI0_E14") (pintype "bidirectional"))
      (node (ref "IC2") (pin "A2") (pinfunction "DQ24_A2") (pintype "bidirectional"))
    )
    (net (code "117") (name "/RAM_D25") (class "Default")
      (node (ref "IC1") (pin "D14") (pinfunction "PI1_D14") (pintype "bidirectional"))
      (node (ref "IC2") (pin "C3") (pinfunction "DQ25_C3") (pintype "bidirectional"))
    )
    (net (code "118") (name "/RAM_D26") (class "Default")
      (node (ref "IC1") (pin "C14") (pinfunction "PI2_C14") (pintype "bidirectional"))
      (node (ref "IC2") (pin "A1") (pinfunction "DQ26_A1") (pintype "bidirectional"))
    )
    (net (code "119") (name "/RAM_D27") (class "Default")
      (node (ref "IC1") (pin "C13") (pinfunction "PI3_C13") (pintype "bidirectional"))
      (node (ref "IC2") (pin "C2") (pinfunction "DQ27_C2") (pintype "bidirectional"))
    )
    (net (code "120") (name "/RAM_D28") (class "Default")
      (node (ref "IC1") (pin "C3") (pinfunction "PI6_C3") (pintype "bidirectional"))
      (node (ref "IC2") (pin "B1") (pinfunction "DQ28_B1") (pintype "bidirectional"))
    )
    (net (code "121") (name "/RAM_D29") (class "Default")
      (node (ref "IC1") (pin "C2") (pinfunction "PI7_C2") (pintype "bidirectional"))
      (node (ref "IC2") (pin "D2") (pinfunction "DQ29_D2") (pintype "bidirectional"))
    )
    (net (code "122") (name "/RAM_D30") (class "Default")
      (node (ref "IC1") (pin "D3") (pinfunction "PI9_D3") (pintype "bidirectional"))
      (node (ref "IC2") (pin "D3") (pinfunction "DQ30_D3") (pintype "bidirectional"))
    )
    (net (code "123") (name "/RAM_D31") (class "Default")
      (node (ref "IC1") (pin "E3") (pinfunction "PI10_E3") (pintype "bidirectional"))
      (node (ref "IC2") (pin "E2") (pinfunction "DQ31_E2") (pintype "bidirectional"))
    )
    (net (code "124") (name "/RAM_M0") (class "Default")
      (node (ref "IC1") (pin "A4") (pinfunction "PE0_A4") (pintype "bidirectional"))
      (node (ref "IC2") (pin "K9") (pinfunction "DQM0_K9") (pintype "bidirectional"))
    )
    (net (code "125") (name "/RAM_M1") (class "Default")
      (node (ref "IC1") (pin "A3") (pinfunction "PE1_A3") (pintype "bidirectional"))
      (node (ref "IC2") (pin "K1") (pinfunction "DQM1_K1") (pintype "bidirectional"))
    )
    (net (code "126") (name "/RAM_M2") (class "Default")
      (node (ref "IC1") (pin "D4") (pinfunction "PI4_D4") (pintype "bidirectional"))
      (node (ref "IC2") (pin "F8") (pinfunction "DQM2_F8") (pintype "bidirectional"))
    )
    (net (code "127") (name "/RAM_M3") (class "Default")
      (node (ref "IC1") (pin "C4") (pinfunction "PI5_C4") (pintype "bidirectional"))
      (node (ref "IC2") (pin "F2") (pinfunction "DQM3_F2") (pintype "bidirectional"))
    )
    (net (code "128") (name "/RAM_~{CAS}") (class "Default")
      (node (ref "IC1") (pin "B7") (pinfunction "PG15_B7") (pintype "bidirectional"))
      (node (ref "IC2") (pin "K7") (pinfunction "~{CAS}_K7") (pintype "bidirectional"))
    )
    (net (code "129") (name "/RAM_~{CS}") (class "Default")
      (node (ref "IC1") (pin "G4") (pinfunction "PH3_G4") (pintype "bidirectional"))
      (node (ref "IC2") (pin "J8") (pinfunction "~{CS}_J8") (pintype "bidirectional"))
    )
    (net (code "130") (name "/RAM_~{RAS}") (class "Default")
      (node (ref "IC1") (pin "R6") (pinfunction "PF11_R6") (pintype "bidirectional"))
      (node (ref "IC2") (pin "J9") (pinfunction "~{RAS}_J9") (pintype "bidirectional"))
    )
    (net (code "131") (name "/RAM_~{WE}") (class "Default")
      (node (ref "IC1") (pin "J4") (pinfunction "PH5_J4") (pintype "bidirectional"))
      (node (ref "IC2") (pin "K8") (pinfunction "~{WE}_K8") (pintype "bidirectional"))
    )
    (net (code "132") (name "/SAI_BCK") (class "Default")
      (node (ref "IC1") (pin "B2") (pinfunction "PE5_B2") (pintype "bidirectional"))
      (node (ref "U2") (pin "36") (pinfunction "BCKDA_36") (pintype "bidirectional"))
      (node (ref "U2") (pin "7") (pinfunction "BCKAD_7") (pintype "bidirectional"))
    )
    (net (code "133") (name "/SAI_LRCK") (class "Default")
      (node (ref "IC1") (pin "B1") (pinfunction "PE4_B1") (pintype "bidirectional"))
      (node (ref "U2") (pin "35") (pinfunction "LRCKDA_35") (pintype "bidirectional"))
      (node (ref "U2") (pin "6") (pinfunction "LRCKAD_6") (pintype "bidirectional"))
    )
    (net (code "134") (name "/SAI_MCLK") (class "Default")
      (node (ref "IC1") (pin "J14") (pinfunction "PG7_J14") (pintype "bidirectional"))
      (node (ref "U2") (pin "41") (pinfunction "SCKI_41") (pintype "bidirectional"))
    )
    (net (code "135") (name "/SAI_SDI") (class "Default")
      (node (ref "IC1") (pin "A1") (pinfunction "PE3_A1") (pintype "bidirectional"))
      (node (ref "U2") (pin "8") (pinfunction "DOUT1_8") (pintype "bidirectional"))
    )
    (net (code "136") (name "/SAI_SDO") (class "Default")
      (node (ref "IC1") (pin "B3") (pinfunction "PE6_B3") (pintype "bidirectional"))
      (node (ref "U2") (pin "37") (pinfunction "DIN1_37") (pintype "bidirectional"))
    )
    (net (code "137") (name "/SPI3_MISO") (class "Default")
      (node (ref "IC1") (pin "B13") (pinfunction "PC11_B13") (pintype "bidirectional"))
      (node (ref "JP2") (pin "20") (pinfunction "20_20") (pintype "passive"))
    )
    (net (code "138") (name "/SPI3_MOSI") (class "Default")
      (node (ref "IC1") (pin "A12") (pinfunction "PC12_A12") (pintype "bidirectional"))
      (node (ref "JP2") (pin "22") (pinfunction "22_22") (pintype "passive"))
    )
    (net (code "139") (name "/SPI3_SCK") (class "Default")
      (node (ref "IC1") (pin "B14") (pinfunction "PC10_B14") (pintype "bidirectional"))
      (node (ref "JP2") (pin "18") (pinfunction "18_18") (pintype "passive"))
    )
    (net (code "140") (name "/SPI6_MISO") (class "Default")
      (node (ref "IC1") (pin "A9") (pinfunction "PB4_A9") (pintype "bidirectional"))
      (node (ref "JP2") (pin "19") (pinfunction "19_19") (pintype "passive"))
    )
    (net (code "141") (name "/SPI6_MOSI") (class "Default")
      (node (ref "IC1") (pin "A7") (pinfunction "PG14_A7") (pintype "bidirectional"))
      (node (ref "JP2") (pin "21") (pinfunction "21_21") (pintype "passive"))
    )
    (net (code "142") (name "/SPI6_SCK") (class "Default")
      (node (ref "IC1") (pin "A8") (pinfunction "PG13_A8") (pintype "bidirectional"))
      (node (ref "JP2") (pin "17") (pinfunction "17_17") (pintype "passive"))
    )
    (net (code "143") (name "/SWDCLK") (class "Default")
      (node (ref "IC1") (pin "A14") (pinfunction "PA14_A14") (pintype "bidirectional"))
      (node (ref "J2") (pin "4") (pinfunction "SWDCLK/TCK_4") (pintype "bidirectional"))
    )
    (net (code "144") (name "/SWDIO") (class "Default")
      (node (ref "IC1") (pin "A15") (pinfunction "PA13_A15") (pintype "bidirectional"))
      (node (ref "J2") (pin "2") (pinfunction "SWDIO/TMS_2") (pintype "bidirectional"))
    )
    (net (code "145") (name "/SWO") (class "Default")
      (node (ref "IC1") (pin "A10") (pinfunction "PB3_A10") (pintype "bidirectional"))
      (node (ref "J2") (pin "6") (pinfunction "SWO/TDO_6") (pintype "bidirectional"))
    )
    (net (code "146") (name "/TIM2_CH1") (class "Default")
      (node (ref "IC1") (pin "A13") (pinfunction "PA15_A13") (pintype "bidirectional"))
      (node (ref "JP1") (pin "19") (pinfunction "19_19") (pintype "passive"))
    )
    (net (code "147") (name "/TIM2_CH2") (class "Default")
      (node (ref "IC1") (pin "N2") (pinfunction "PA1_N2") (pintype "bidirectional"))
      (node (ref "JP1") (pin "20") (pinfunction "20_20") (pintype "passive"))
    )
    (net (code "148") (name "/TIM3_CH1") (class "Default")
      (node (ref "IC1") (pin "H15") (pinfunction "PC6_H15") (pintype "bidirectional"))
      (node (ref "JP1") (pin "21") (pinfunction "21_21") (pintype "passive"))
    )
    (net (code "149") (name "/TIM3_CH2") (class "Default")
      (node (ref "IC1") (pin "G15") (pinfunction "PC7_G15") (pintype "bidirectional"))
      (node (ref "JP1") (pin "22") (pinfunction "22_22") (pintype "passive"))
    )
    (net (code "150") (name "/TIM4_CH1") (class "Default")
      (node (ref "IC1") (pin "N13") (pinfunction "PD12_N13") (pintype "bidirectional"))
      (node (ref "JP1") (pin "23") (pinfunction "23_23") (pintype "passive"))
    )
    (net (code "151") (name "/TIM4_CH2") (class "Default")
      (node (ref "IC1") (pin "M15") (pinfunction "PD13_M15") (pintype "bidirectional"))
      (node (ref "JP1") (pin "24") (pinfunction "24_24") (pintype "passive"))
    )
    (net (code "152") (name "/UART5_RX") (class "Default")
      (node (ref "IC1") (pin "A6") (pinfunction "PB5_A6") (pintype "bidirectional"))
      (node (ref "JP2") (pin "15") (pinfunction "15_15") (pintype "passive"))
    )
    (net (code "153") (name "/UART5_TX") (class "Default")
      (node (ref "IC1") (pin "B6") (pinfunction "PB6_B6") (pintype "bidirectional"))
      (node (ref "JP2") (pin "13") (pinfunction "13_13") (pintype "passive"))
    )
    (net (code "154") (name "/UART7_RX") (class "Default")
      (node (ref "IC1") (pin "F15") (pinfunction "PA8_F15") (pintype "bidirectional"))
      (node (ref "JP2") (pin "16") (pinfunction "16_16") (pintype "passive"))
    )
    (net (code "155") (name "/UART7_TX") (class "Default")
      (node (ref "IC1") (pin "K1") (pinfunction "PF7_K1") (pintype "bidirectional"))
      (node (ref "JP2") (pin "14") (pinfunction "14_14") (pintype "passive"))
    )
    (net (code "156") (name "/USBD_D+") (class "Default")
      (node (ref "CN1") (pin "3") (pinfunction "D+_3") (pintype "bidirectional"))
      (node (ref "IC1") (pin "B15") (pinfunction "PA12_B15") (pintype "bidirectional"))
      (node (ref "JP2") (pin "7") (pinfunction "7_7") (pintype "passive"))
    )
    (net (code "157") (name "/USBD_D-") (class "Default")
      (node (ref "CN1") (pin "2") (pinfunction "D-_2") (pintype "bidirectional"))
      (node (ref "IC1") (pin "C15") (pinfunction "PA11_C15") (pintype "bidirectional"))
      (node (ref "JP2") (pin "5") (pinfunction "5_5") (pintype "passive"))
    )
    (net (code "158") (name "/USBD_ID") (class "Default")
      (node (ref "CN1") (pin "4") (pinfunction "ID_4") (pintype "bidirectional"))
      (node (ref "IC1") (pin "D15") (pinfunction "PA10_D15") (pintype "bidirectional"))
      (node (ref "JP2") (pin "9") (pinfunction "9_9") (pintype "passive"))
    )
    (net (code "159") (name "/USBD_VBUS") (class "Default")
      (node (ref "CN1") (pin "1") (pinfunction "VCC_1") (pintype "bidirectional"))
      (node (ref "IC1") (pin "E15") (pinfunction "PA9_E15") (pintype "bidirectional"))
      (node (ref "JP2") (pin "3") (pinfunction "3_3") (pintype "passive"))
    )
    (net (code "160") (name "/USBH_D+") (class "Default")
      (node (ref "IC1") (pin "R15") (pinfunction "PB15_R15") (pintype "bidirectional"))
      (node (ref "JP2") (pin "8") (pinfunction "8_8") (pintype "passive"))
    )
    (net (code "161") (name "/USBH_D-") (class "Default")
      (node (ref "IC1") (pin "R14") (pinfunction "PB14_R14") (pintype "bidirectional"))
      (node (ref "JP2") (pin "6") (pinfunction "6_6") (pintype "passive"))
    )
    (net (code "162") (name "/USBH_ID") (class "Default")
      (node (ref "IC1") (pin "P12") (pinfunction "PB12_P12") (pintype "bidirectional"))
      (node (ref "JP2") (pin "10") (pinfunction "10_10") (pintype "passive"))
    )
    (net (code "163") (name "/USBH_VBUS") (class "Default")
      (node (ref "IC1") (pin "P13") (pinfunction "PB13_P13") (pintype "bidirectional"))
      (node (ref "JP2") (pin "4") (pinfunction "4_4") (pintype "passive"))
    )
    (net (code "164") (name "AGND") (class "Default")
      (node (ref "C11") (pin "2") (pinfunction "2_2") (pintype "passive"))
      (node (ref "C12") (pin "2") (pinfunction "2_2") (pintype "passive"))
      (node (ref "C21") (pin "2") (pinfunction "2_2") (pintype "passive"))
      (node (ref "C24") (pin "2") (pinfunction "2_2") (pintype "passive"))
      (node (ref "C25") (pin "-") (pinfunction "-_-") (pintype "passive"))
      (node (ref "C28") (pin "-") (pinfunction "-_-") (pintype "passive"))
      (node (ref "C29") (pin "-") (pinfunction "-_-") (pintype "passive"))
      (node (ref "C30") (pin "-") (pinfunction "-_-") (pintype "passive"))
      (node (ref "C31") (pin "-") (pinfunction "-_-") (pintype "passive"))
      (node (ref "C32") (pin "2") (pinfunction "2_2") (pintype "passive"))
      (node (ref "C33") (pin "2") (pinfunction "2_2") (pintype "passive"))
      (node (ref "C34") (pin "2") (pinfunction "2_2") (pintype "passive"))
      (node (ref "C35") (pin "2") (pinfunction "2_2") (pintype "passive"))
      (node (ref "IC1") (pin "M1") (pinfunction "VSSA_M1") (pintype "bidirectional"))
      (node (ref "IC1") (pin "N1") (pinfunction "VREF-_N1") (pintype "bidirectional"))
      (node (ref "JP1") (pin "33") (pinfunction "33_33") (pintype "passive"))
      (node (ref "JP1") (pin "47") (pinfunction "47_47") (pintype "passive"))
      (node (ref "JP1") (pin "48") (pinfunction "48_48") (pintype "passive"))
      (node (ref "JP2") (pin "25") (pinfunction "25_25") (pintype "passive"))
      (node (ref "JP2") (pin "26") (pinfunction "26_26") (pintype "passive"))
      (node (ref "JP2") (pin "29") (pinfunction "29_29") (pintype "passive"))
      (node (ref "JP2") (pin "47") (pinfunction "47_47") (pintype "passive"))
      (node (ref "JP2") (pin "48") (pinfunction "48_48") (pintype "passive"))
      (node (ref "L1") (pin "1") (pinfunction "1_1") (pintype "passive"))
      (node (ref "U2") (pin "16") (pinfunction "AGNDDA1_16") (pintype "bidirectional"))
      (node (ref "U2") (pin "2") (pinfunction "AGNDAD2_2") (pintype "bidirectional"))
      (node (ref "U2") (pin "33") (pinfunction "AGNDDA2_33") (pintype "bidirectional"))
      (node (ref "U2") (pin "50") (pinfunction "AGNDAD1_50") (pintype "bidirectional"))
      (node (ref "U2") (pin "EP") (pinfunction "AGND_EP") (pintype "bidirectional"))
    )
    (net (code "165") (name "GND") (class "Default")
      (node (ref "C1") (pin "2") (pinfunction "2_2") (pintype "passive"))
      (node (ref "C10") (pin "2") (pinfunction "2_2") (pintype "passive"))
      (node (ref "C13") (pin "2") (pinfunction "2_2") (pintype "passive"))
      (node (ref "C14") (pin "2") (pinfunction "2_2") (pintype "passive"))
      (node (ref "C16") (pin "-") (pinfunction "-_-") (pintype "passive"))
      (node (ref "C18") (pin "-") (pinfunction "-_-") (pintype "passive"))
      (node (ref "C19") (pin "-") (pinfunction "-_-") (pintype "passive"))
      (node (ref "C2") (pin "2") (pinfunction "2_2") (pintype "passive"))
      (node (ref "C20") (pin "2") (pinfunction "2_2") (pintype "passive"))
      (node (ref "C22") (pin "2") (pinfunction "2_2") (pintype "passive"))
      (node (ref "C23") (pin "2") (pinfunction "2_2") (pintype "passive"))
      (node (ref "C26") (pin "2") (pinfunction "2_2") (pintype "passive"))
      (node (ref "C3") (pin "2") (pinfunction "2_2") (pintype "passive"))
      (node (ref "C36") (pin "2") (pinfunction "2_2") (pintype "passive"))
      (node (ref "C37") (pin "2") (pinfunction "2_2") (pintype "passive"))
      (node (ref "C38") (pin "1") (pinfunction "1_1") (pintype "passive"))
      (node (ref "C39") (pin "2") (pinfunction "2_2") (pintype "passive"))
      (node (ref "C4") (pin "2") (pinfunction "2_2") (pintype "passive"))
      (node (ref "C40") (pin "2") (pinfunction "2_2") (pintype "passive"))
      (node (ref "C5") (pin "2") (pinfunction "2_2") (pintype "passive"))
      (node (ref "C6") (pin "2") (pinfunction "2_2") (pintype "passive"))
      (node (ref "C7") (pin "2") (pinfunction "2_2") (pintype "passive"))
      (node (ref "C8") (pin "2") (pinfunction "2_2") (pintype "passive"))
      (node (ref "C9") (pin "2") (pinfunction "2_2") (pintype "passive"))
      (node (ref "C90") (pin "2") (pinfunction "2_2") (pintype "passive"))
      (node (ref "CN1") (pin "5") (pinfunction "GND_5") (pintype "bidirectional"))
      (node (ref "CN1") (pin "G") (pinfunction "SHIELD_G") (pintype "bidirectional"))
      (node (ref "CN1") (pin "G2") (pinfunction "SHIELD_G2") (pintype "bidirectional"))
      (node (ref "CN1") (pin "G3") (pinfunction "SHIELD_G3") (pintype "bidirectional"))
      (node (ref "CN1") (pin "G4") (pinfunction "SHIELD_G4") (pintype "bidirectional"))
      (node (ref "IC1") (pin "D5") (pinfunction "VSS_1_D5") (pintype "bidirectional"))
      (node (ref "IC1") (pin "D7") (pinfunction "VSS_2_D7") (pintype "bidirectional"))
      (node (ref "IC1") (pin "D8") (pinfunction "VSS_3_D8") (pintype "bidirectional"))
      (node (ref "IC1") (pin "D9") (pinfunction "VSS_4_D9") (pintype "bidirectional"))
      (node (ref "IC1") (pin "F10") (pinfunction "VSS_10_F10") (pintype "bidirectional"))
      (node (ref "IC1") (pin "F12") (pinfunction "VSS_11_F12") (pintype "bidirectional"))
      (node (ref "IC1") (pin "F2") (pinfunction "VSS_5_F2") (pintype "bidirectional"))
      (node (ref "IC1") (pin "F6") (pinfunction "VSS_6_F6") (pintype "bidirectional"))
      (node (ref "IC1") (pin "F7") (pinfunction "VSS_7_F7") (pintype "bidirectional"))
      (node (ref "IC1") (pin "F8") (pinfunction "VSS_8_F8") (pintype "bidirectional"))
      (node (ref "IC1") (pin "F9") (pinfunction "VSS_9_F9") (pintype "bidirectional"))
      (node (ref "IC1") (pin "G10") (pinfunction "VSS_17_G10") (pintype "bidirectional"))
      (node (ref "IC1") (pin "G12") (pinfunction "VSS_18_G12") (pintype "bidirectional"))
      (node (ref "IC1") (pin "G2") (pinfunction "VSS_12_G2") (pintype "bidirectional"))
      (node (ref "IC1") (pin "G6") (pinfunction "VSS_13_G6") (pintype "bidirectional"))
      (node (ref "IC1") (pin "G7") (pinfunction "VSS_14_G7") (pintype "bidirectional"))
      (node (ref "IC1") (pin "G8") (pinfunction "VSS_15_G8") (pintype "bidirectional"))
      (node (ref "IC1") (pin "G9") (pinfunction "VSS_16_G9") (pintype "bidirectional"))
      (node (ref "IC1") (pin "H10") (pinfunction "VSS_23_H10") (pintype "bidirectional"))
      (node (ref "IC1") (pin "H12") (pinfunction "VSS_24_H12") (pintype "bidirectional"))
      (node (ref "IC1") (pin "H6") (pinfunction "VSS_19_H6") (pintype "bidirectional"))
      (node (ref "IC1") (pin "H7") (pinfunction "VSS_20_H7") (pintype "bidirectional"))
      (node (ref "IC1") (pin "H8") (pinfunction "VSS_21_H8") (pintype "bidirectional"))
      (node (ref "IC1") (pin "H9") (pinfunction "VSS_22_H9") (pintype "bidirectional"))
      (node (ref "IC1") (pin "J10") (pinfunction "VSS_29_J10") (pintype "bidirectional"))
      (node (ref "IC1") (pin "J6") (pinfunction "VSS_25_J6") (pintype "bidirectional"))
      (node (ref "IC1") (pin "J7") (pinfunction "VSS_26_J7") (pintype "bidirectional"))
      (node (ref "IC1") (pin "J8") (pinfunction "VSS_27_J8") (pintype "bidirectional"))
      (node (ref "IC1") (pin "J9") (pinfunction "VSS_28_J9") (pintype "bidirectional"))
      (node (ref "IC1") (pin "K10") (pinfunction "VSS_34_K10") (pintype "bidirectional"))
      (node (ref "IC1") (pin "K6") (pinfunction "VSS_30_K6") (pintype "bidirectional"))
      (node (ref "IC1") (pin "K7") (pinfunction "VSS_31_K7") (pintype "bidirectional"))
      (node (ref "IC1") (pin "K8") (pinfunction "VSS_32_K8") (pintype "bidirectional"))
      (node (ref "IC1") (pin "K9") (pinfunction "VSS_33_K9") (pintype "bidirectional"))
      (node (ref "IC1") (pin "L4") (pinfunction "VSS_35_L4") (pintype "bidirectional"))
      (node (ref "IC1") (pin "M8") (pinfunction "VSS_36_M8") (pintype "bidirectional"))
      (node (ref "IC1") (pin "M9") (pinfunction "VSS_37_M9") (pintype "bidirectional"))
      (node (ref "IC2") (pin "A3") (pinfunction "VSS_1_A3") (pintype "bidirectional"))
      (node (ref "IC2") (pin "B3") (pinfunction "VSSQ_1_B3") (pintype "bidirectional"))
      (node (ref "IC2") (pin "B8") (pinfunction "VSSQ_2_B8") (pintype "bidirectional"))
      (node (ref "IC2") (pin "C1") (pinfunction "VSSQ_3_C1") (pintype "bidirectional"))
      (node (ref "IC2") (pin "D1") (pinfunction "VSSQ_4_D1") (pintype "bidirectional"))
      (node (ref "IC2") (pin "E9") (pinfunction "VSSQ_5_E9") (pintype "bidirectional"))
      (node (ref "IC2") (pin "F1") (pinfunction "VSS_2_F1") (pintype "bidirectional"))
      (node (ref "IC2") (pin "L3") (pinfunction "VSS_3_L3") (pintype "bidirectional"))
      (node (ref "IC2") (pin "L9") (pinfunction "VSSQ_6_L9") (pintype "bidirectional"))
      (node (ref "IC2") (pin "M1") (pinfunction "VSSQ_7_M1") (pintype "bidirectional"))
      (node (ref "IC2") (pin "N1") (pinfunction "VSSQ_8_N1") (pintype "bidirectional"))
      (node (ref "IC2") (pin "P3") (pinfunction "VSSQ_9_P3") (pintype "bidirectional"))
      (node (ref "IC2") (pin "P8") (pinfunction "VSSQ_10_P8") (pintype "bidirectional"))
      (node (ref "IC2") (pin "R3") (pinfunction "VSS_4_R3") (pintype "bidirectional"))
      (node (ref "IC9") (pin "4") (pinfunction "VSS_4") (pintype "bidirectional"))
      (node (ref "J2") (pin "3") (pinfunction "GND_3") (pintype "bidirectional"))
      (node (ref "J2") (pin "5") (pinfunction "GND_5") (pintype "bidirectional"))
      (node (ref "J2") (pin "7") (pinfunction "GND_7") (pintype "bidirectional"))
      (node (ref "J2") (pin "9") (pinfunction "GND_9") (pintype "bidirectional"))
      (node (ref "JP1") (pin "15") (pinfunction "15_15") (pintype "passive"))
      (node (ref "JP1") (pin "16") (pinfunction "16_16") (pintype "passive"))
      (node (ref "JP2") (pin "11") (pinfunction "11_11") (pintype "passive"))
      (node (ref "JP2") (pin "12") (pinfunction "12_12") (pintype "passive"))
      (node (ref "L1") (pin "2") (pinfunction "2_2") (pintype "passive"))
      (node (ref "R1") (pin "1") (pinfunction "1_1") (pintype "passive"))
      (node (ref "U2") (pin "11") (pinfunction "DGND_11") (pintype "bidirectional"))
      (node (ref "U2") (pin "47") (pinfunction "DGND_47") (pintype "bidirectional"))
      (node (ref "U3") (pin "1") (pinfunction "ADJ_1") (pintype "input"))
    )
    (net (code "166") (name "Net-(IC1-PH0-_OSC_IN)") (class "Default")
      (node (ref "C22") (pin "1") (pinfunction "1_1") (pintype "passive"))
      (node (ref "IC1") (pin "G1") (pinfunction "PH0-_OSC_IN_G1") (pintype "bidirectional"))
      (node (ref "Y1") (pin "2") (pinfunction "2_2") (pintype "passive"))
    )
    (net (code "167") (name "Net-(IC1-PH1-_OSC___OUT)") (class "Default")
      (node (ref "C23") (pin "1") (pinfunction "1_1") (pintype "passive"))
      (node (ref "IC1") (pin "H1") (pinfunction "PH1-_OSC___OUT_H1") (pintype "bidirectional"))
      (node (ref "Y1") (pin "1") (pinfunction "1_1") (pintype "passive"))
    )
    (net (code "168") (name "Net-(IC1-VCAP_1)") (class "Default")
      (node (ref "C13") (pin "1") (pinfunction "1_1") (pintype "passive"))
      (node (ref "IC1") (pin "F13") (pinfunction "VCAP_1_F13") (pintype "bidirectional"))
    )
    (net (code "169") (name "Net-(IC1-VCAP_2)") (class "Default")
      (node (ref "C14") (pin "1") (pinfunction "1_1") (pintype "passive"))
      (node (ref "IC1") (pin "M10") (pinfunction "VCAP_2_M10") (pintype "bidirectional"))
    )
    (net (code "170") (name "Net-(U2-VREFAD1)") (class "Default")
      (node (ref "C29") (pin "+") (pinfunction "+_+") (pintype "passive"))
      (node (ref "U2") (pin "59") (pinfunction "VREFAD1_59") (pintype "bidirectional"))
    )
    (net (code "171") (name "Net-(U2-VREFAD2)") (class "Default")
      (node (ref "C28") (pin "+") (pinfunction "+_+") (pintype "passive"))
      (node (ref "U2") (pin "60") (pinfunction "VREFAD2_60") (pintype "bidirectional"))
    )
    (net (code "172") (name "unconnected-(IC1-PB2-PadM6)") (class "Default")
      (node (ref "IC1") (pin "M6") (pinfunction "PB2_M6") (pintype "bidirectional"))
    )
    (net (code "173") (name "unconnected-(IC1-PB9-PadB4)") (class "Default")
      (node (ref "IC1") (pin "B4") (pinfunction "PB9_B4") (pintype "bidirectional"))
    )
    (net (code "174") (name "unconnected-(IC1-PD3-PadD11)") (class "Default")
      (node (ref "IC1") (pin "D11") (pinfunction "PD3_D11") (pintype "bidirectional"))
    )
    (net (code "175") (name "unconnected-(IC1-PD4-PadD10)") (class "Default")
      (node (ref "IC1") (pin "D10") (pinfunction "PD4_D10") (pintype "bidirectional"))
    )
    (net (code "176") (name "unconnected-(IC1-PD5-PadC11)") (class "Default")
      (node (ref "IC1") (pin "C11") (pinfunction "PD5_C11") (pintype "bidirectional"))
    )
    (net (code "177") (name "unconnected-(IC1-PD6-PadB11)") (class "Default")
      (node (ref "IC1") (pin "B11") (pinfunction "PD6_B11") (pintype "bidirectional"))
    )
    (net (code "178") (name "unconnected-(IC1-PD7-PadA11)") (class "Default")
      (node (ref "IC1") (pin "A11") (pinfunction "PD7_A11") (pintype "bidirectional"))
    )
    (net (code "179") (name "unconnected-(IC1-PD11-PadN14)") (class "Default")
      (node (ref "IC1") (pin "N14") (pinfunction "PD11_N14") (pintype "bidirectional"))
    )
    (net (code "180") (name "unconnected-(IC1-PG9-PadC10)") (class "Default")
      (node (ref "IC1") (pin "C10") (pinfunction "PG9_C10") (pintype "bidirectional"))
    )
    (net (code "181") (name "unconnected-(IC1-PH6-PadM11)") (class "Default")
      (node (ref "IC1") (pin "M11") (pinfunction "PH6_M11") (pintype "bidirectional"))
    )
    (net (code "182") (name "unconnected-(IC1-PH7-PadN12)") (class "Default")
      (node (ref "IC1") (pin "N12") (pinfunction "PH7_N12") (pintype "bidirectional"))
    )
    (net (code "183") (name "unconnected-(IC1-PI8-PadD2)") (class "Default")
      (node (ref "IC1") (pin "D2") (pinfunction "PI8_D2") (pintype "bidirectional"))
    )
    (net (code "184") (name "unconnected-(IC1-VBAT-PadC1)") (class "Default")
      (node (ref "IC1") (pin "C1") (pinfunction "VBAT_C1") (pintype "bidirectional"))
    )
    (net (code "185") (name "unconnected-(IC2-NC_1-PadE3)") (class "Default")
      (node (ref "IC2") (pin "E3") (pinfunction "NC_1_E3") (pintype "bidirectional"))
    )
    (net (code "186") (name "unconnected-(IC2-NC_2-PadE7)") (class "Default")
      (node (ref "IC2") (pin "E7") (pinfunction "NC_2_E7") (pintype "bidirectional"))
    )
    (net (code "187") (name "unconnected-(IC2-NC_3-PadH7)") (class "Default")
      (node (ref "IC2") (pin "H7") (pinfunction "NC_3_H7") (pintype "bidirectional"))
    )
    (net (code "188") (name "unconnected-(IC2-NC_4-PadK2)") (class "Default")
      (node (ref "IC2") (pin "K2") (pinfunction "NC_4_K2") (pintype "bidirectional"))
    )
    (net (code "189") (name "unconnected-(IC2-NC_5-PadK3)") (class "Default")
      (node (ref "IC2") (pin "K3") (pinfunction "NC_5_K3") (pintype "bidirectional"))
    )
    (net (code "190") (name "unconnected-(J2-NC{slash}TDI-Pad8)") (class "Default")
      (node (ref "J2") (pin "8") (pinfunction "NC/TDI_8") (pintype "bidirectional"))
    )
    (net (code "191") (name "unconnected-(U2-DIN2-Pad38)") (class "Default")
      (node (ref "U2") (pin "38") (pinfunction "DIN2_38") (pintype "bidirectional"))
    )
    (net (code "192") (name "unconnected-(U2-DIN3-Pad39)") (class "Default")
      (node (ref "U2") (pin "39") (pinfunction "DIN3_39") (pintype "bidirectional"))
    )
    (net (code "193") (name "unconnected-(U2-DIN4-Pad40)") (class "Default")
      (node (ref "U2") (pin "40") (pinfunction "DIN4_40") (pintype "bidirectional"))
    )
    (net (code "194") (name "unconnected-(U2-DOUT2-Pad9)") (class "Default")
      (node (ref "U2") (pin "9") (pinfunction "DOUT2_9") (pintype "bidirectional"))
    )
    (net (code "195") (name "unconnected-(U2-DOUT3-Pad10)") (class "Default")
      (node (ref "U2") (pin "10") (pinfunction "DOUT3_10") (pintype "bidirectional"))
    )
    (net (code "196") (name "unconnected-(U2-OVF-Pad5)") (class "Default")
      (node (ref "U2") (pin "5") (pinfunction "OVF_5") (pintype "bidirectional"))
    )
    (net (code "197") (name "unconnected-(U2-ZERO-Pad13)") (class "Default")
      (node (ref "U2") (pin "13") (pinfunction "ZERO_13") (pintype "bidirectional"))
    )
  )
)
